# Car-layout_Rev_03_-In_Pros.net
KiCad netlist of a schematic drawn in EAGLE
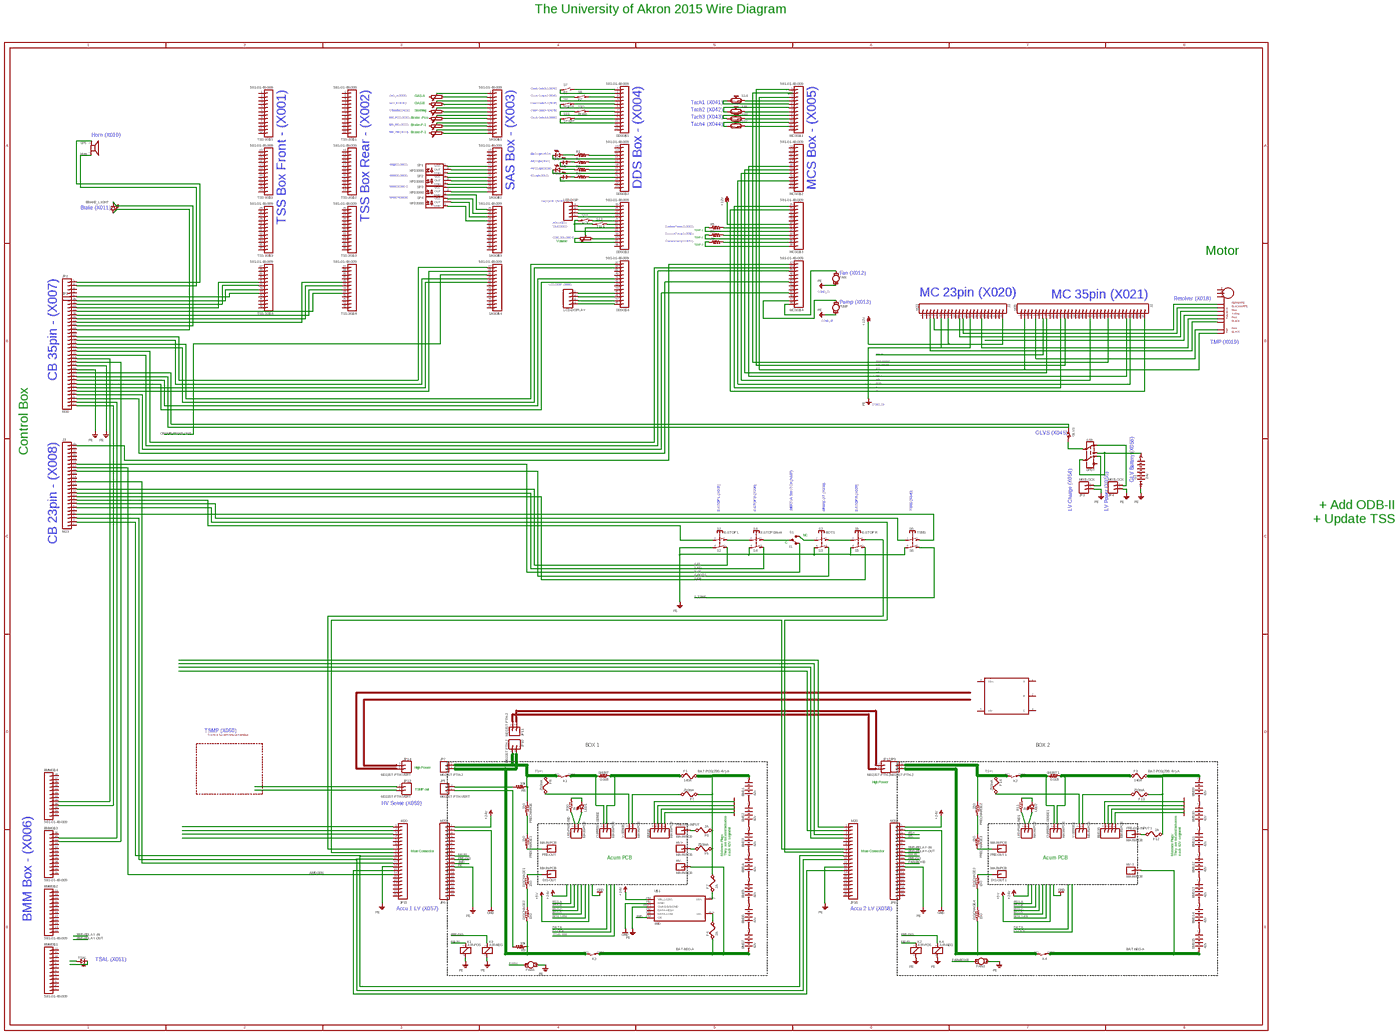
[diagram p0: schematic, sheet 1, overview]
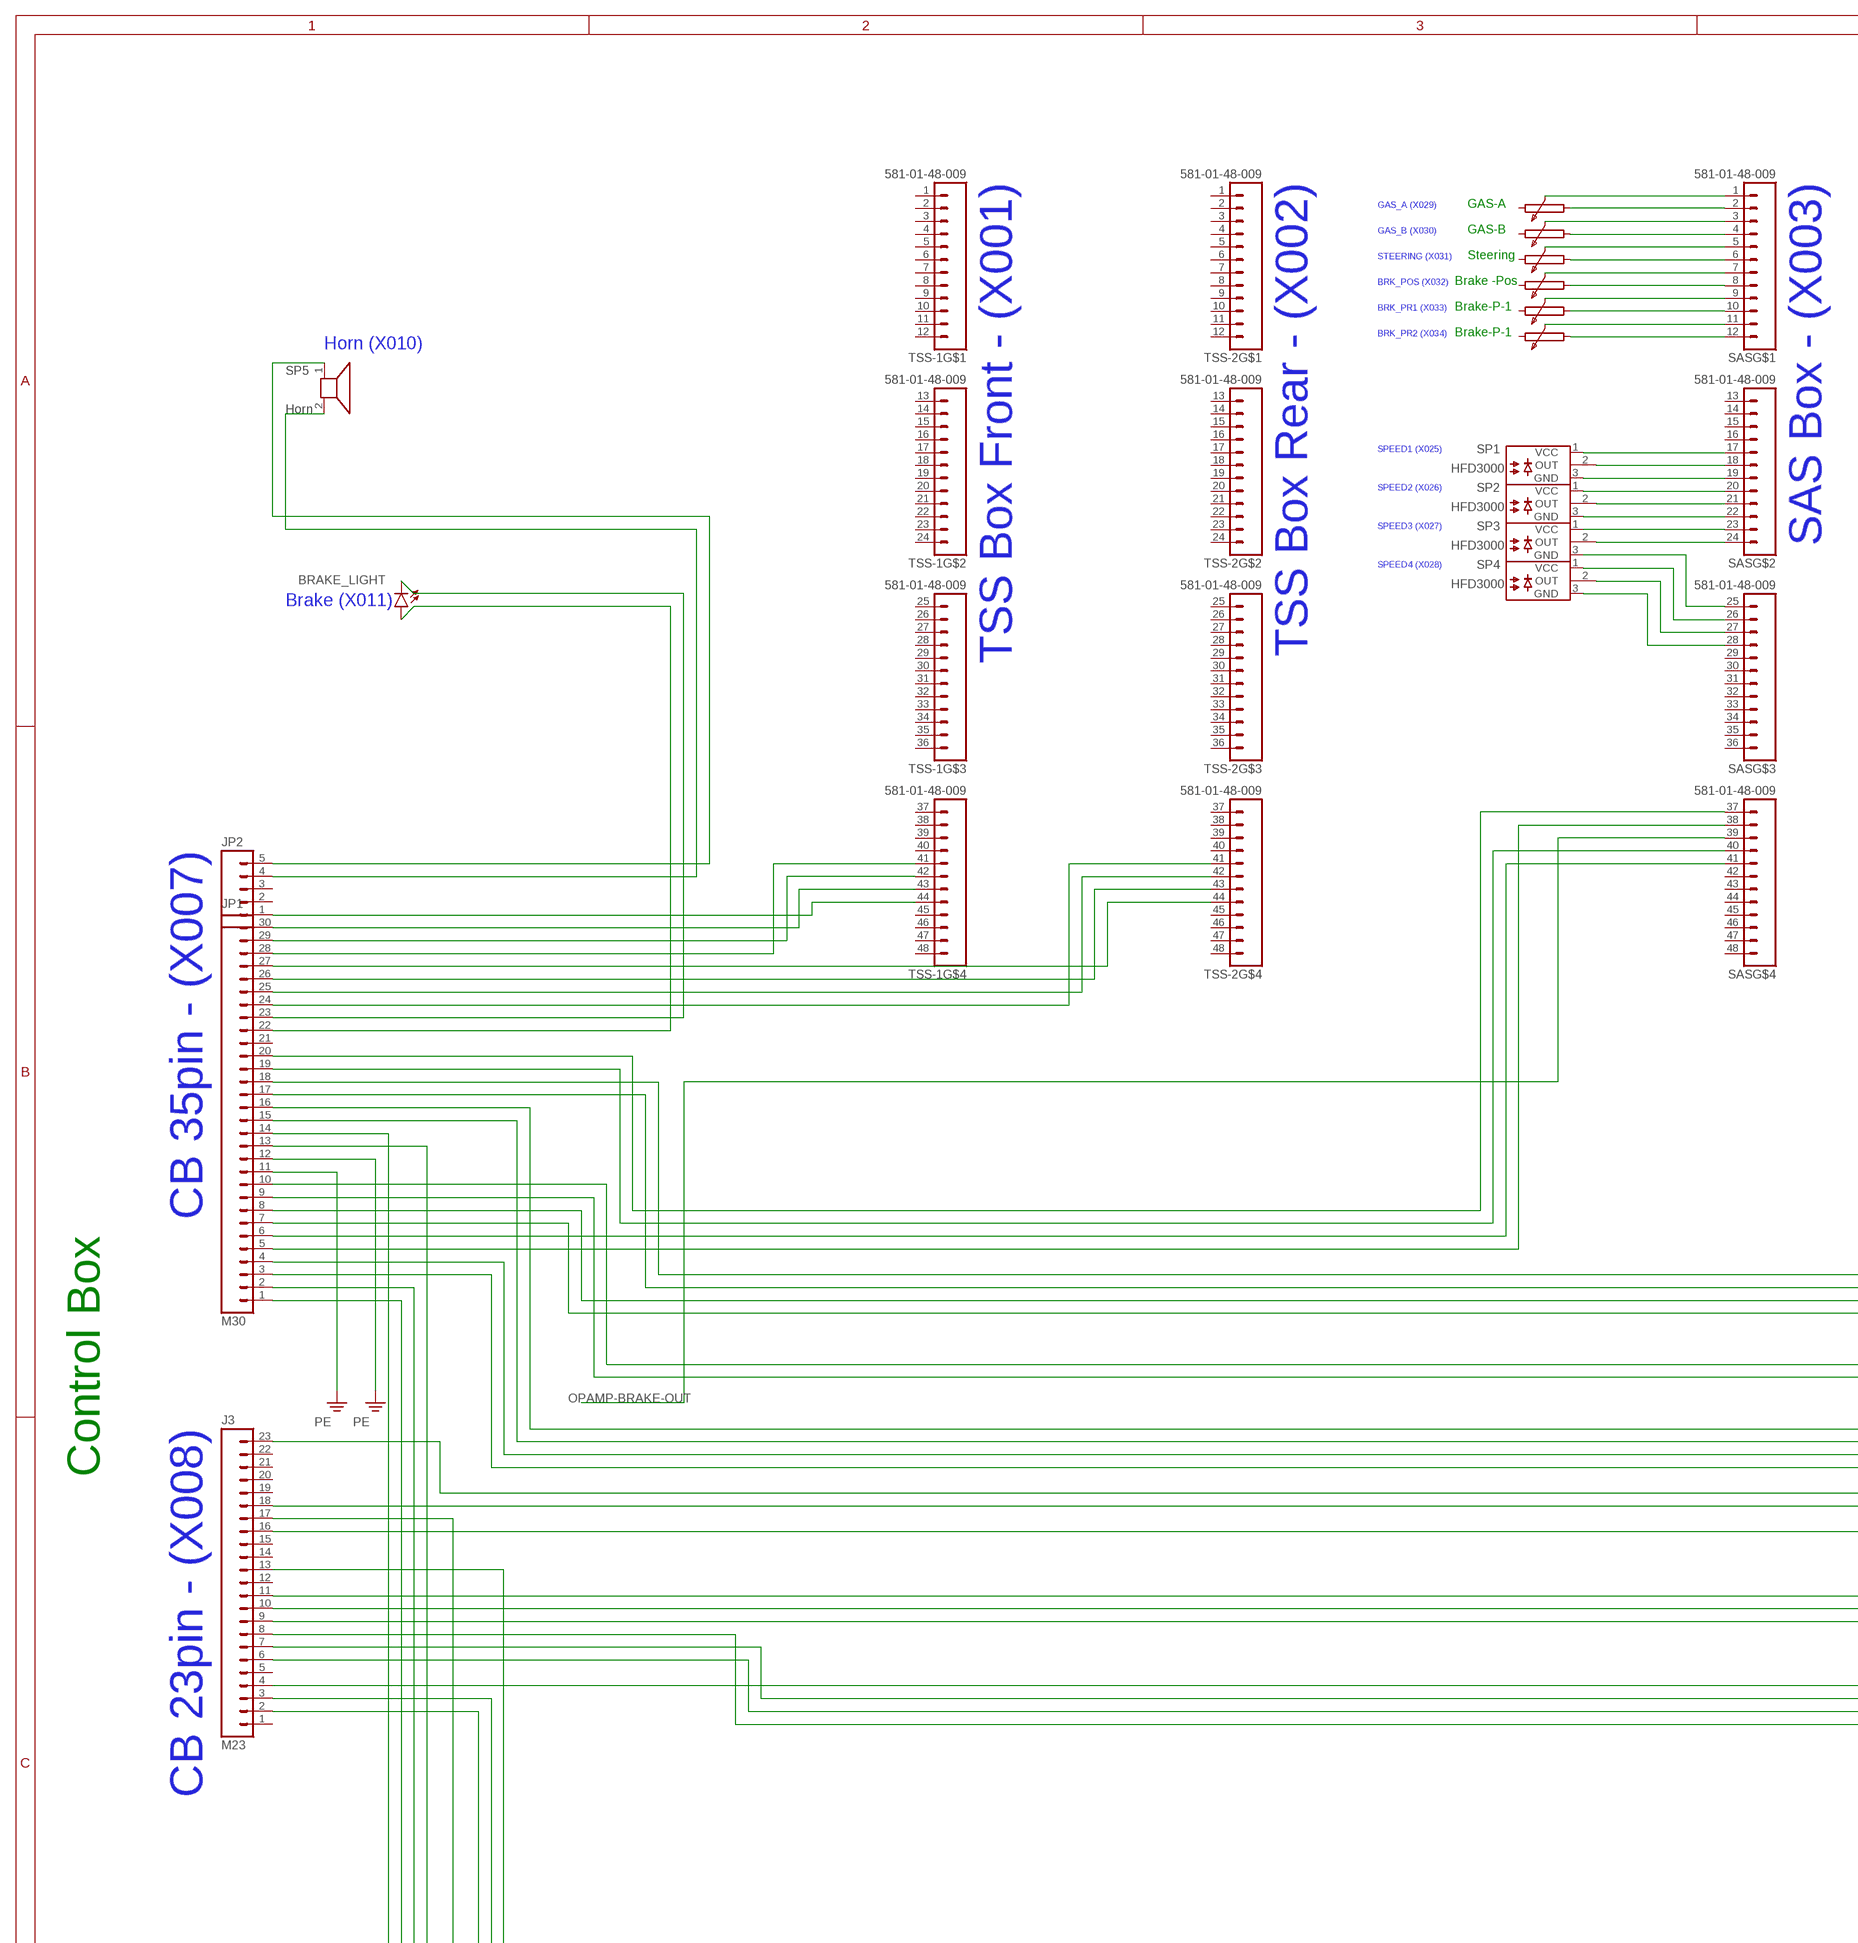
[diagram p1: schematic, sheet 1, part 1 of 6]
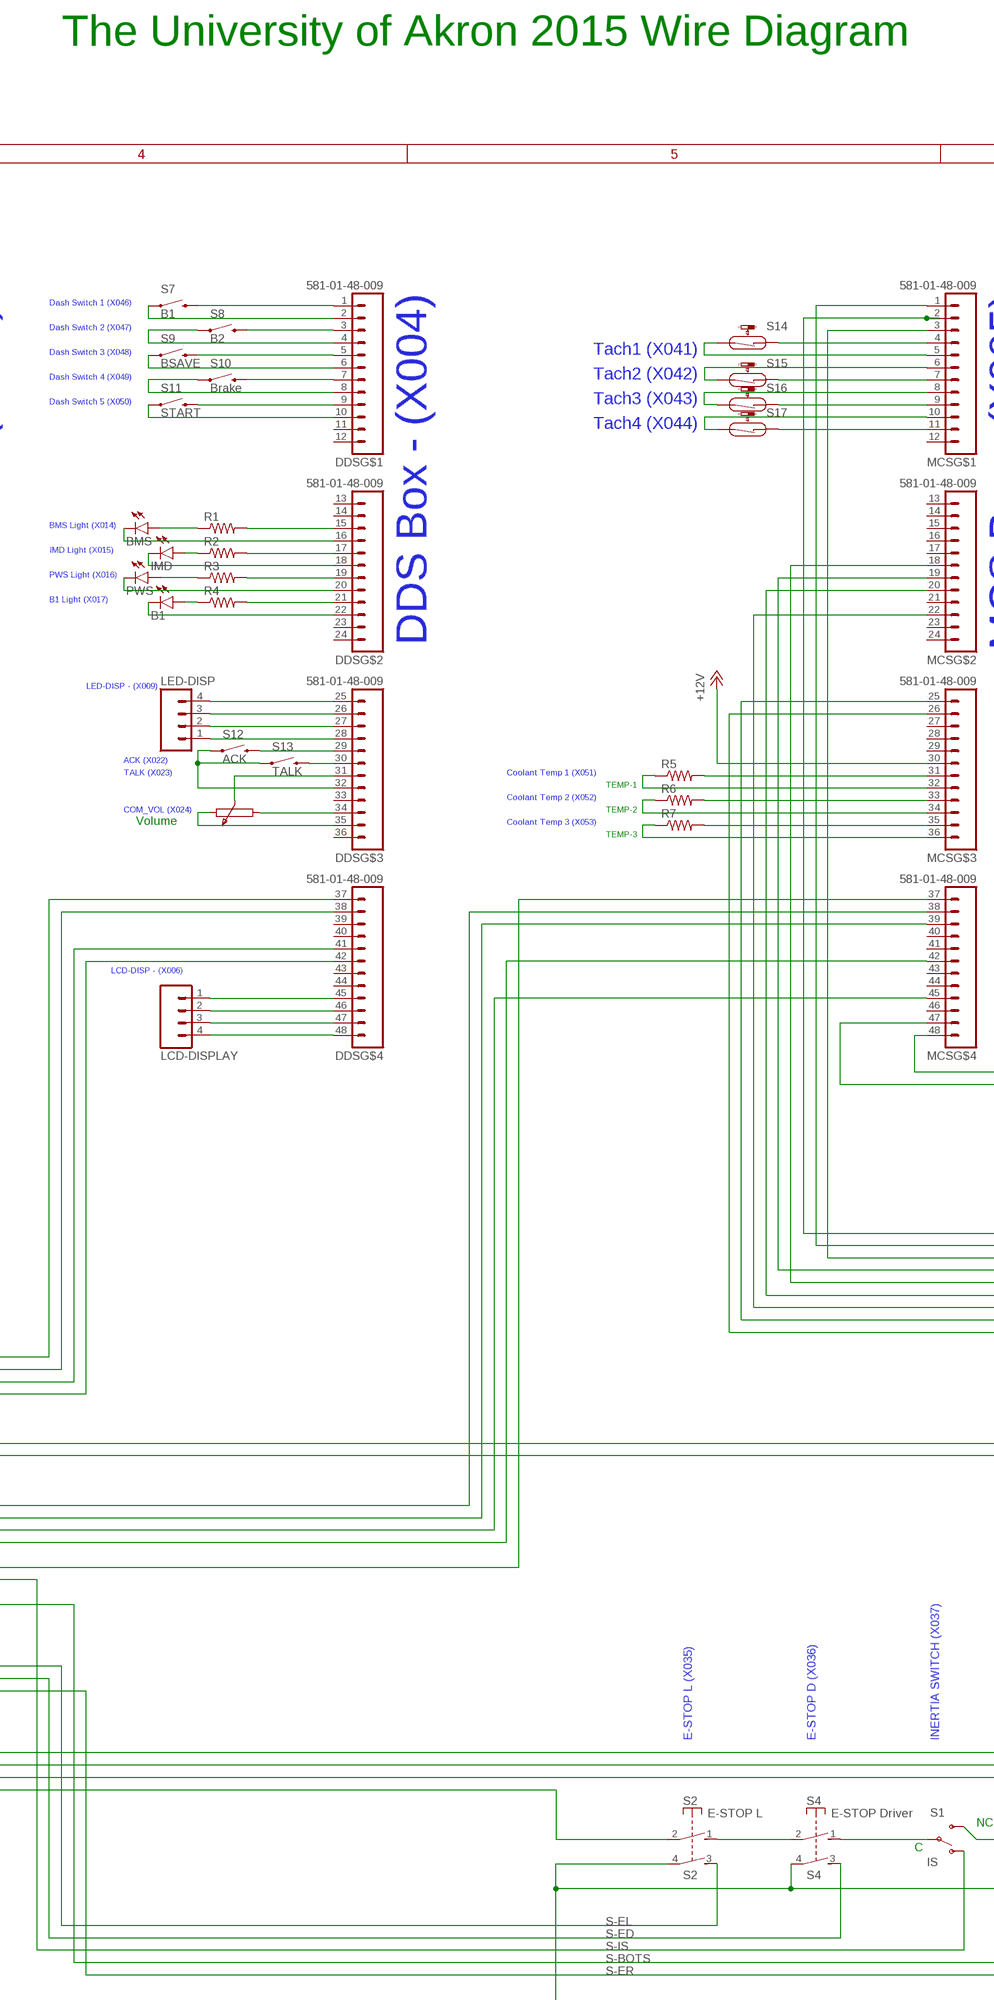
[diagram p2: schematic, sheet 1, part 2 of 6]
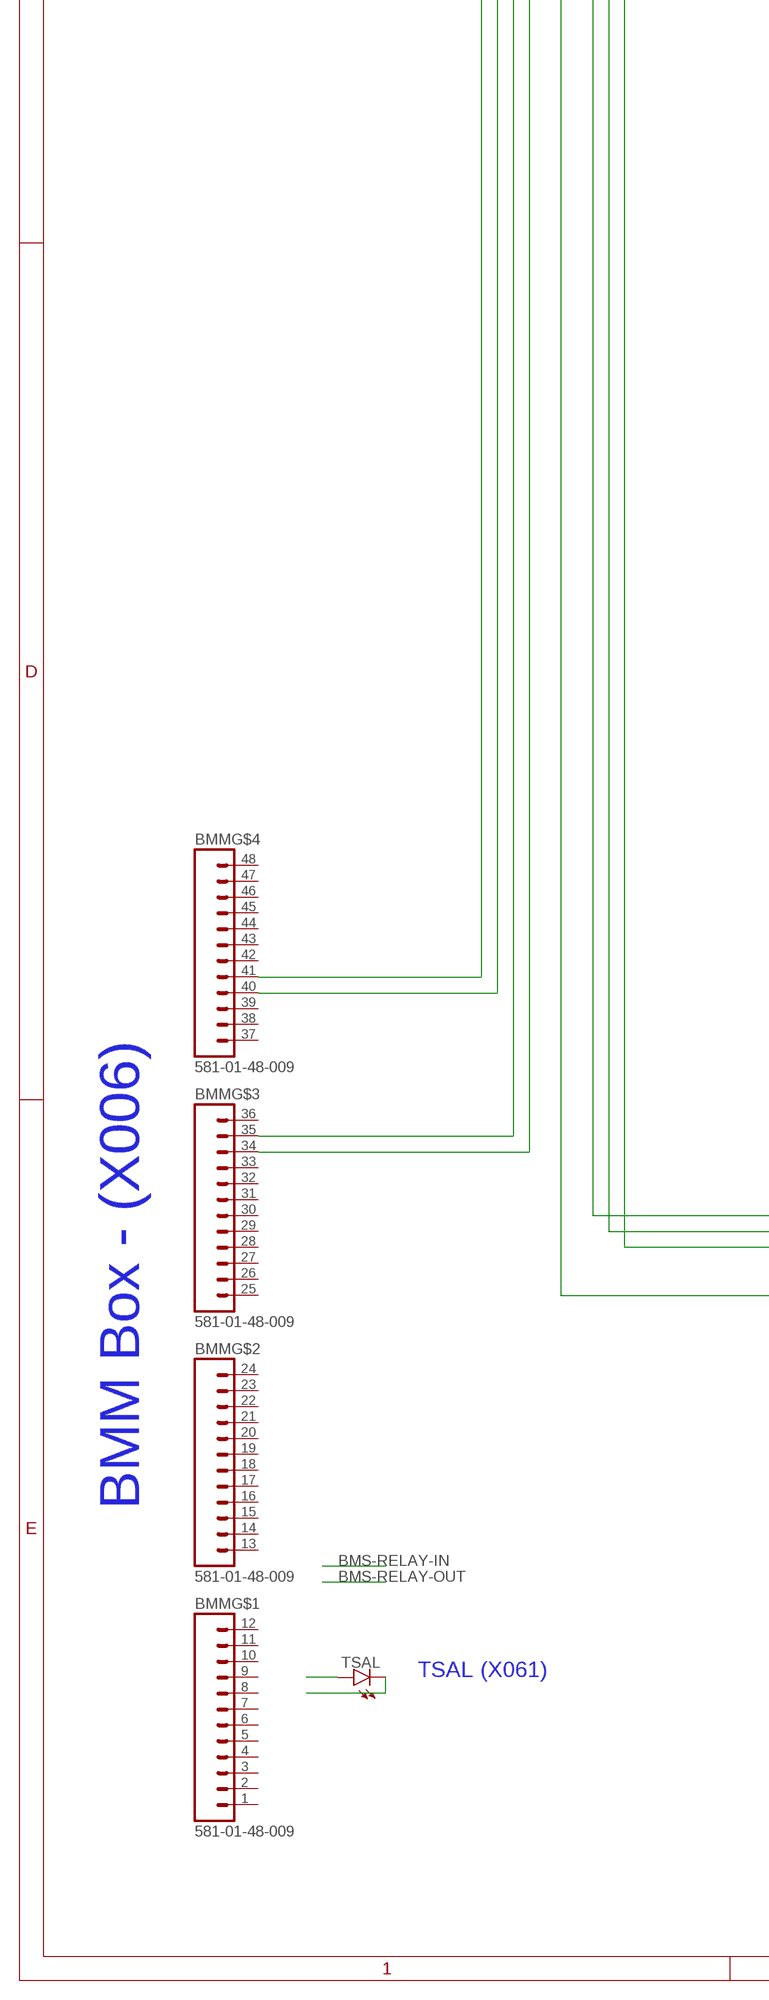
[diagram p3: schematic, sheet 1, part 3 of 6]
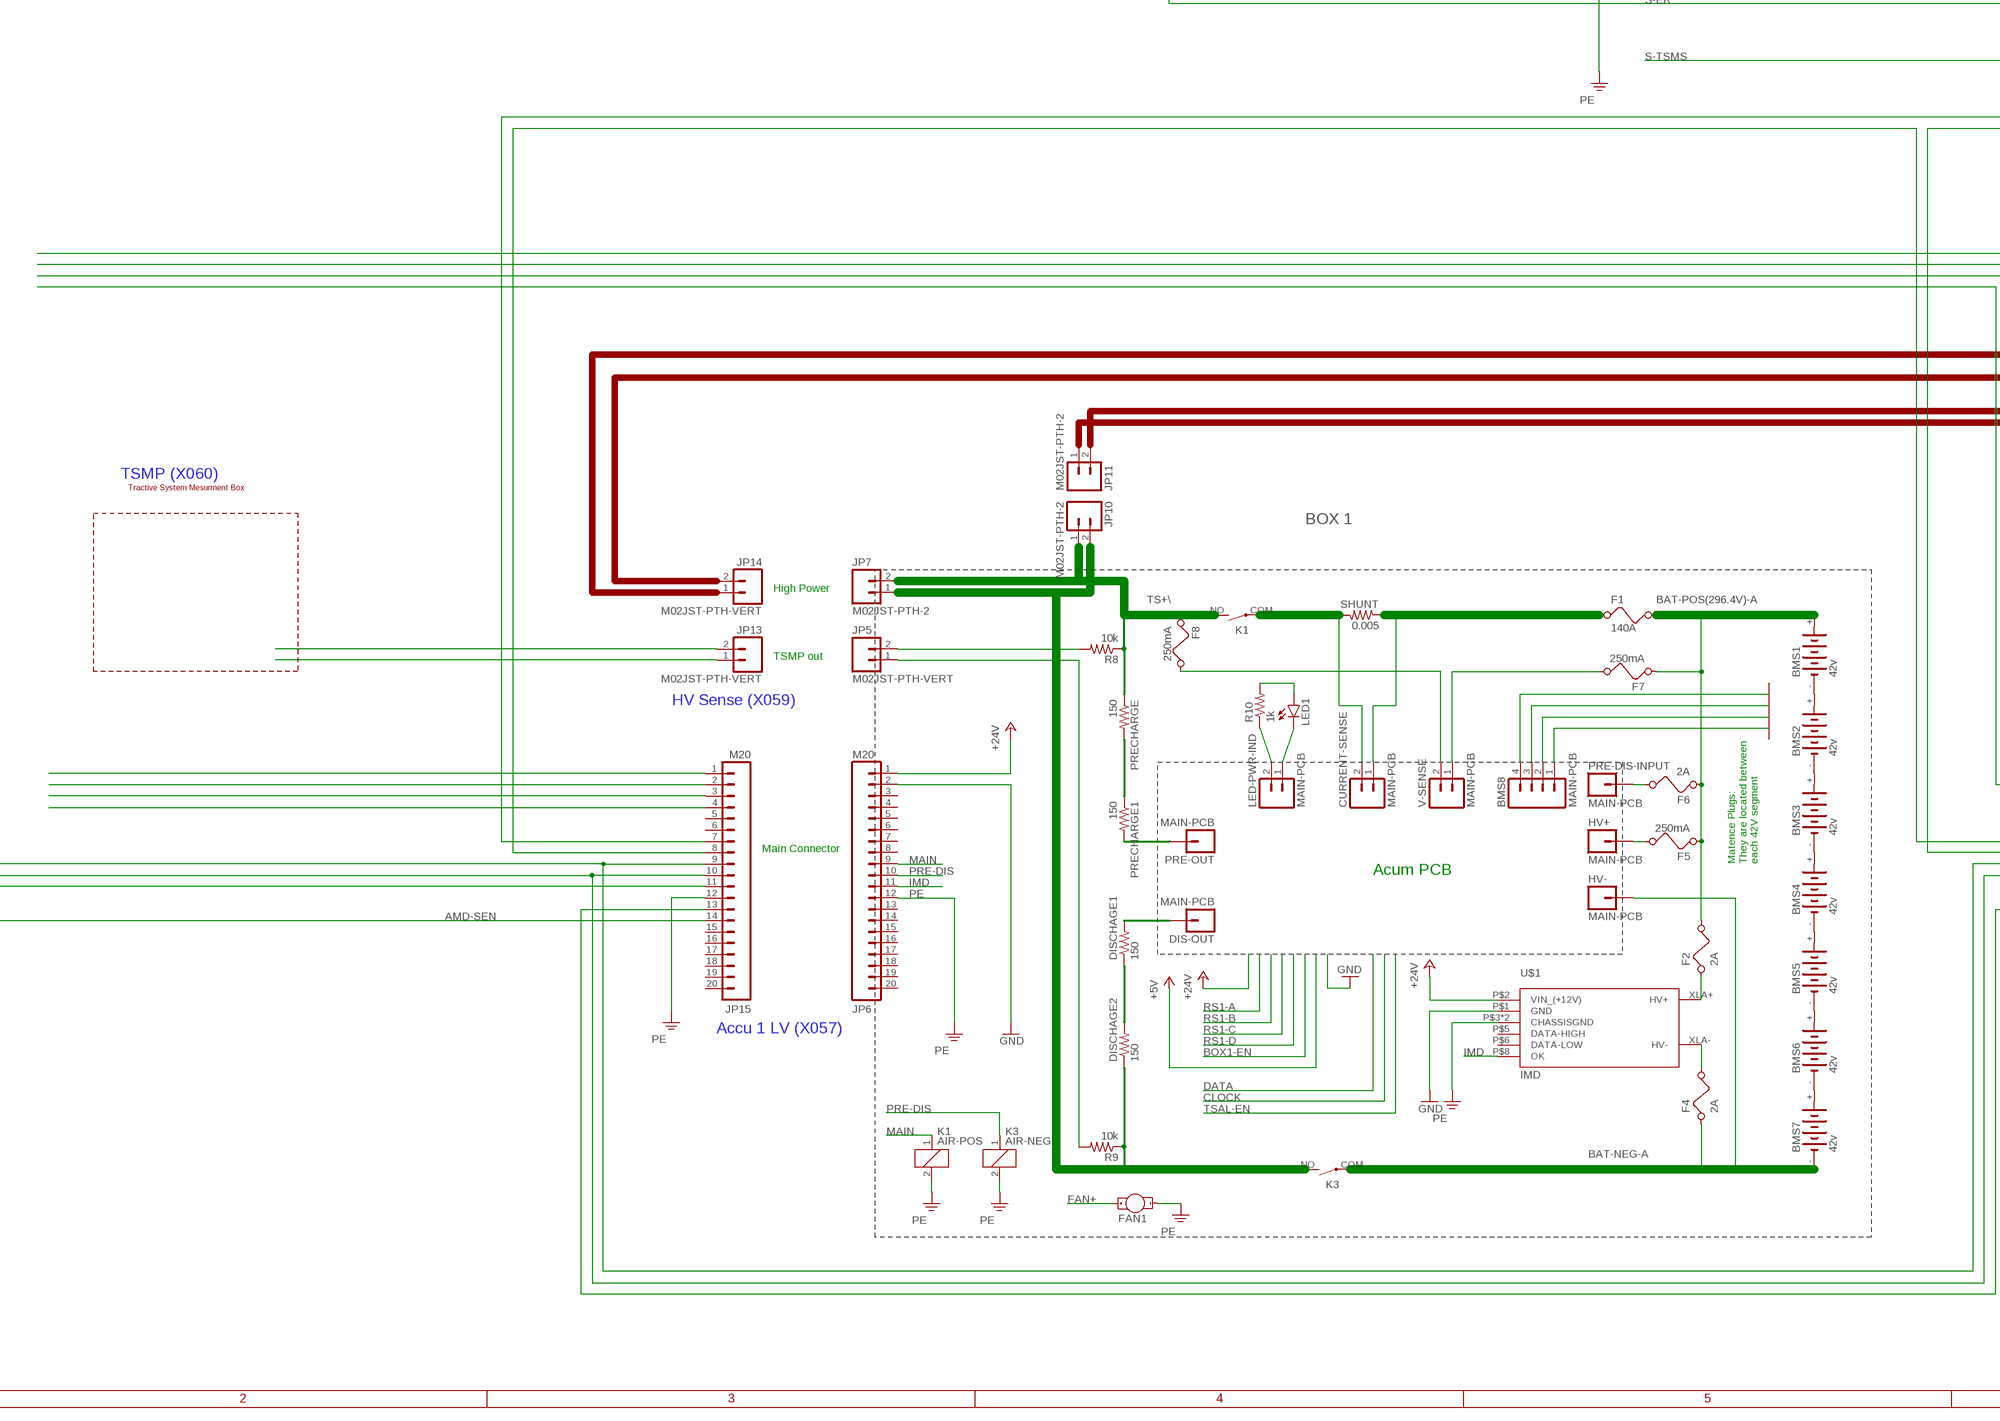
[diagram p4: schematic, sheet 1, part 4 of 6]
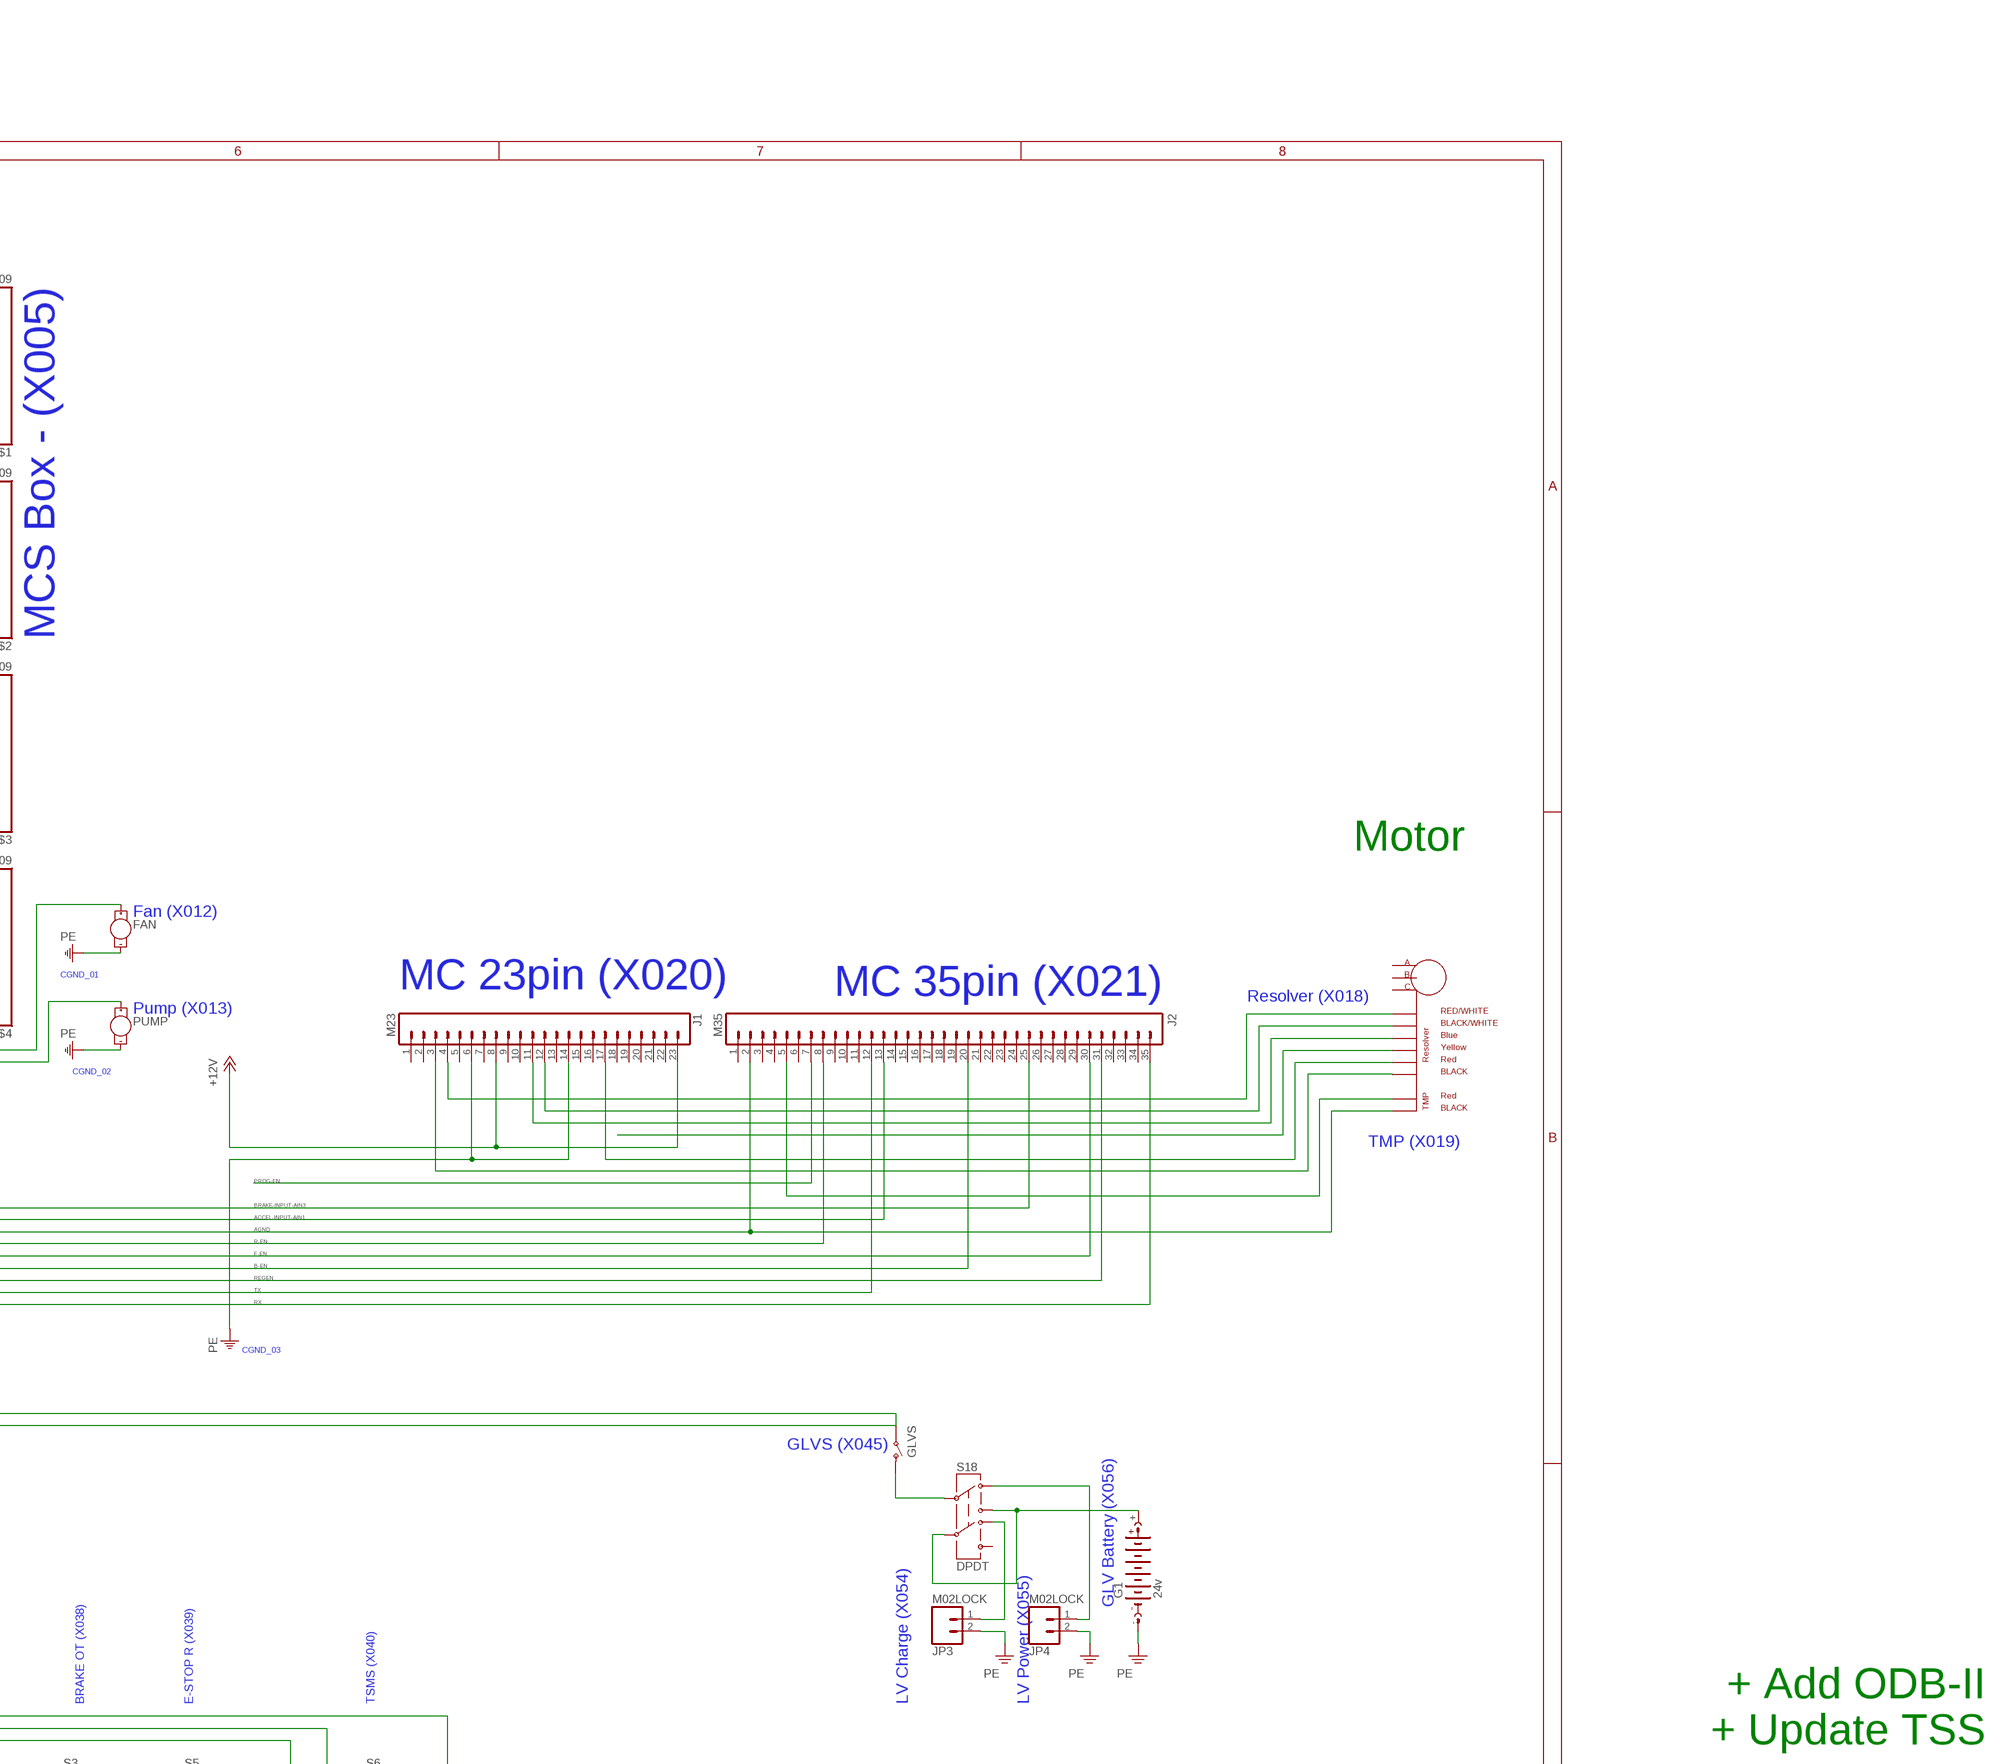
[diagram p5: schematic, sheet 1, part 5 of 6]
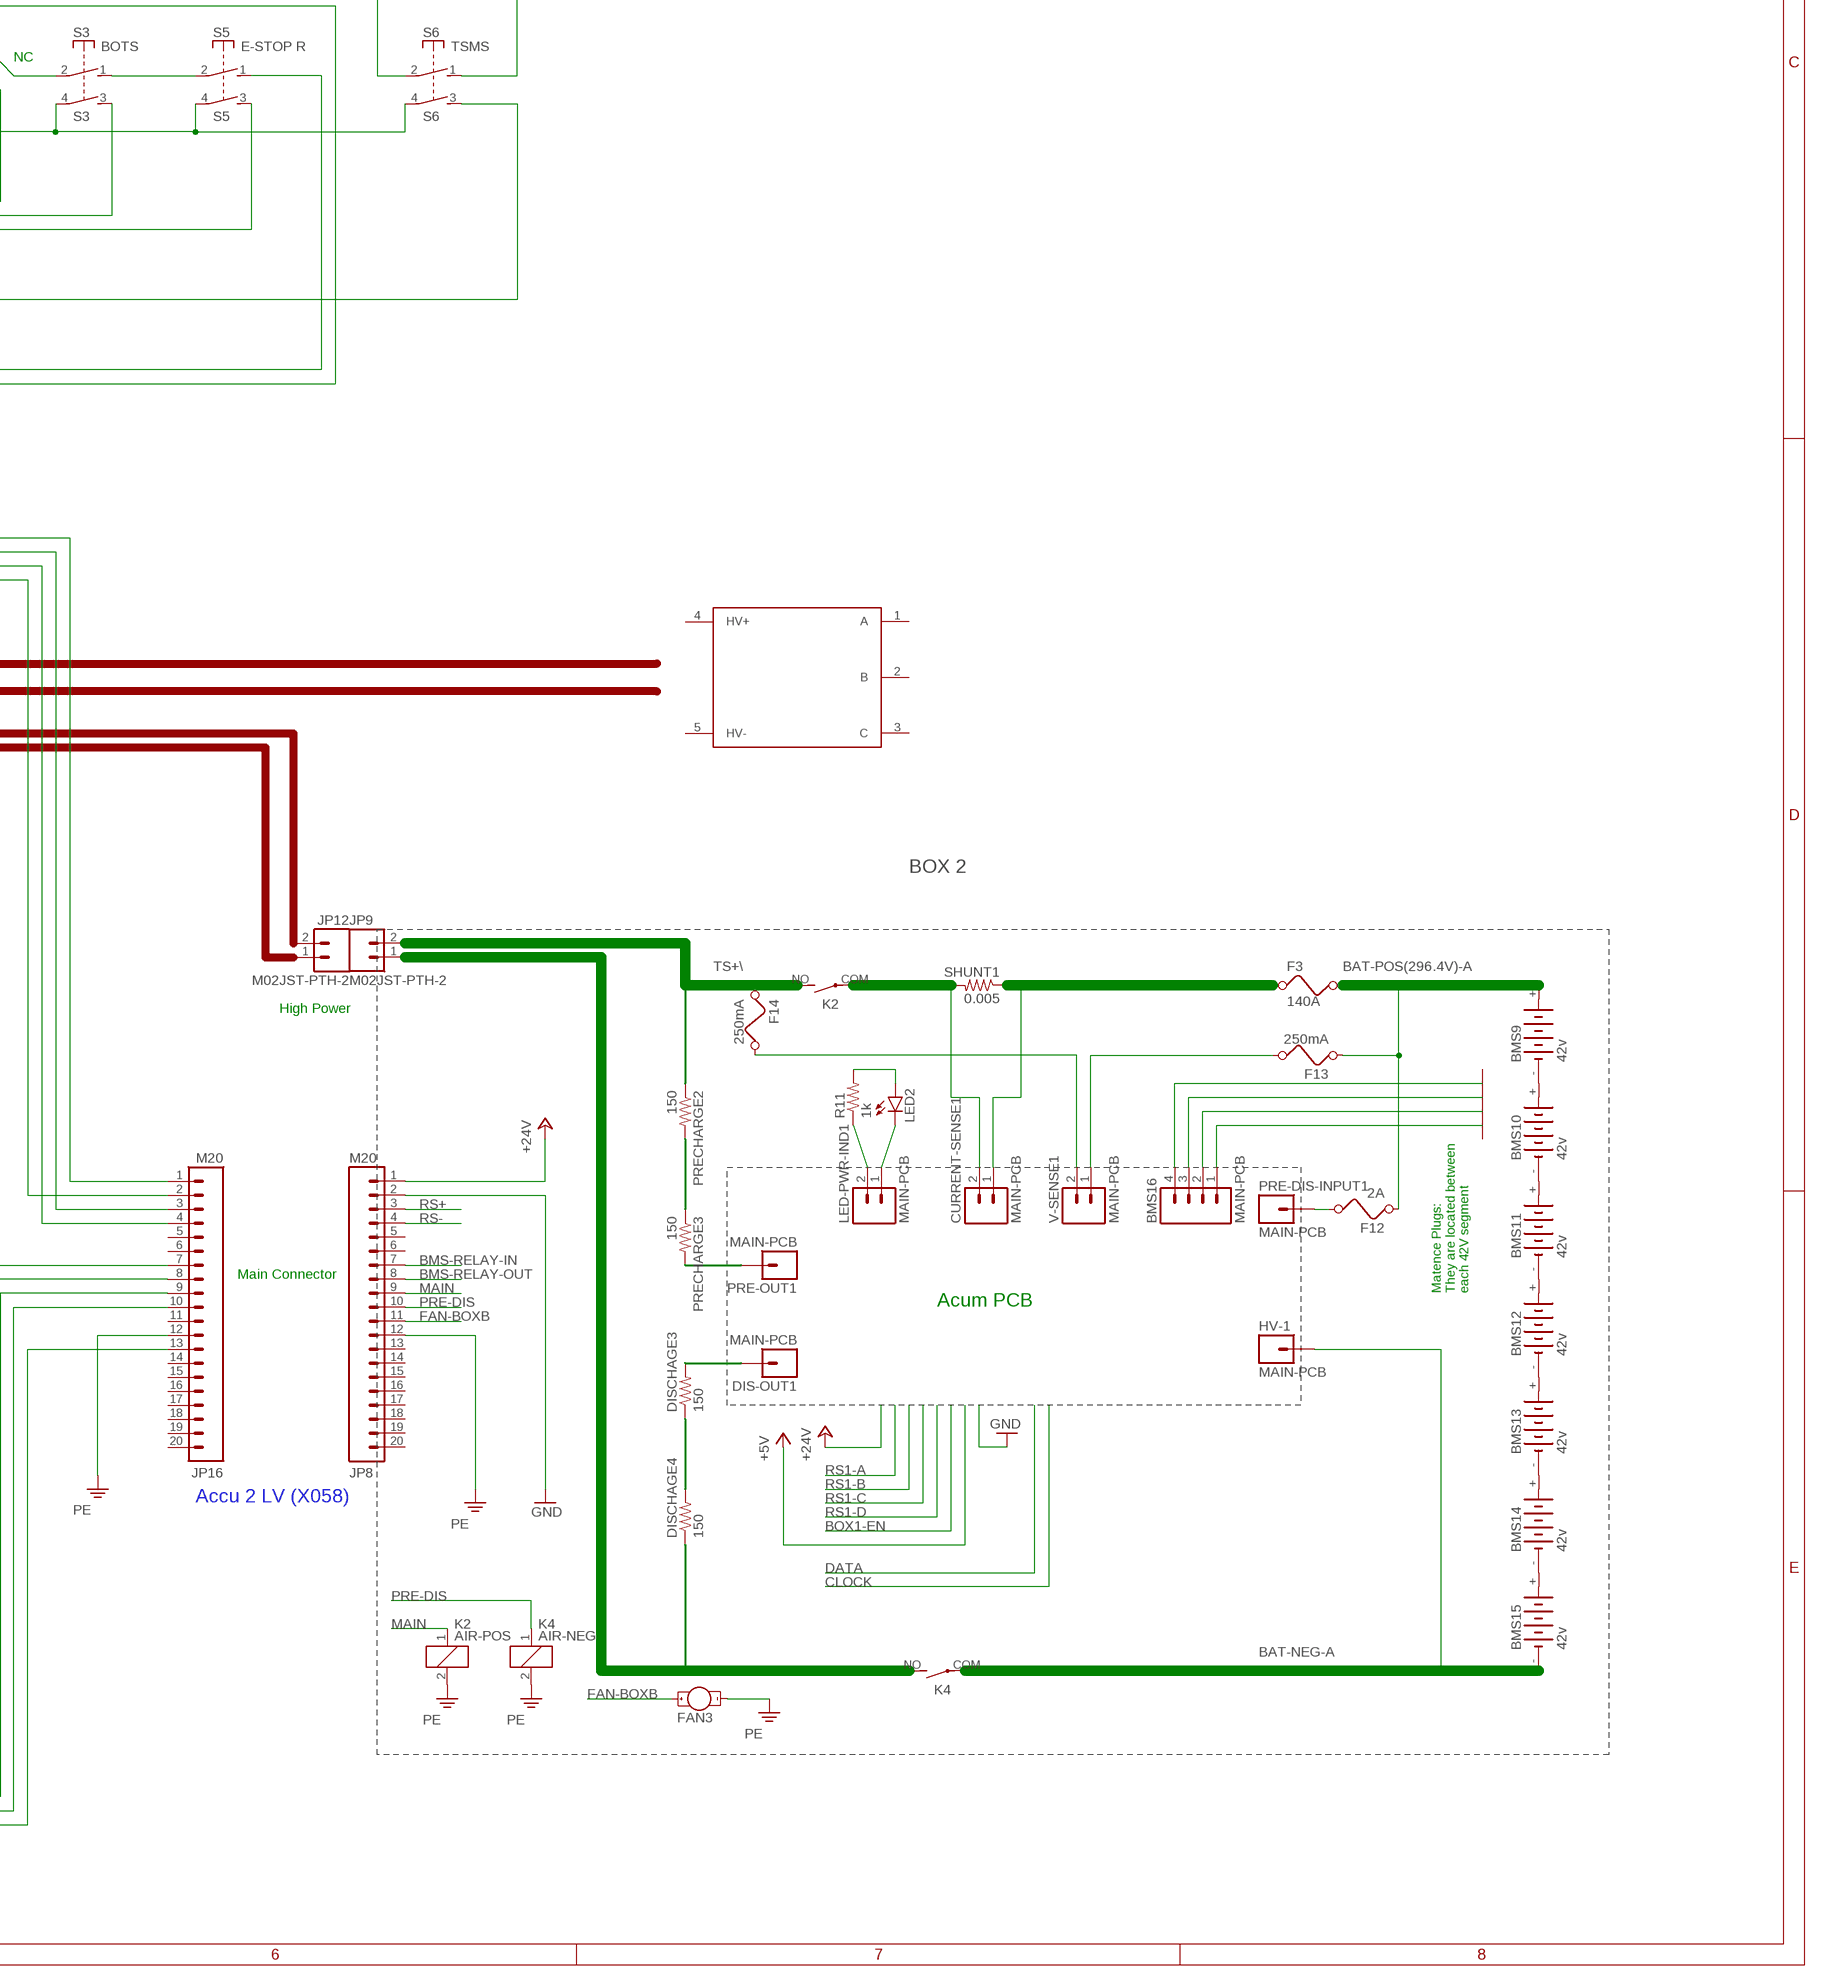
[diagram p6: schematic, sheet 1, part 6 of 6]

(export (version "E")
  (design (tool "Eeschema 10.0.6"))
  (components
    (comp (ref "B1")
      (value "LED5MM")
      (footprint "eagle-import:LED5MM")
      (libsource (lib "eagle-import") (part "LED5MM"))
    )
    (comp (ref "BMM")
      (value "581-01-48-009")
      (footprint "eagle-import:581-01-48-009")
      (libsource (lib "eagle-import") (part "581-01-48-009"))
    )
    (comp (ref "BMS")
      (value "LED5MM")
      (footprint "eagle-import:LED5MM")
      (libsource (lib "eagle-import") (part "LED5MM"))
    )
    (comp (ref "BMS1")
      (value "42v")
      (footprint "eagle-import:VST4")
      (libsource (lib "eagle-import") (part "VST4V8"))
    )
    (comp (ref "BMS2")
      (value "42v")
      (footprint "eagle-import:VST4")
      (libsource (lib "eagle-import") (part "VST4V8"))
    )
    (comp (ref "BMS3")
      (value "42v")
      (footprint "eagle-import:VST4")
      (libsource (lib "eagle-import") (part "VST4V8"))
    )
    (comp (ref "BMS4")
      (value "42v")
      (footprint "eagle-import:VST4")
      (libsource (lib "eagle-import") (part "VST4V8"))
    )
    (comp (ref "BMS5")
      (value "42v")
      (footprint "eagle-import:VST4")
      (libsource (lib "eagle-import") (part "VST4V8"))
    )
    (comp (ref "BMS6")
      (value "42v")
      (footprint "eagle-import:VST4")
      (libsource (lib "eagle-import") (part "VST4V8"))
    )
    (comp (ref "BMS7")
      (value "42v")
      (footprint "eagle-import:VST4")
      (libsource (lib "eagle-import") (part "VST4V8"))
    )
    (comp (ref "BMS8")
      (value "MAIN-PCB")
      (footprint "eagle-import:1X04_LOCK_LONGPADS")
      (libsource (lib "eagle-import") (part "M04LOCK_LONGPADS"))
    )
    (comp (ref "BMS9")
      (value "42v")
      (footprint "eagle-import:VST4")
      (libsource (lib "eagle-import") (part "VST4V8"))
    )
    (comp (ref "BMS10")
      (value "42v")
      (footprint "eagle-import:VST4")
      (libsource (lib "eagle-import") (part "VST4V8"))
    )
    (comp (ref "BMS11")
      (value "42v")
      (footprint "eagle-import:VST4")
      (libsource (lib "eagle-import") (part "VST4V8"))
    )
    (comp (ref "BMS12")
      (value "42v")
      (footprint "eagle-import:VST4")
      (libsource (lib "eagle-import") (part "VST4V8"))
    )
    (comp (ref "BMS13")
      (value "42v")
      (footprint "eagle-import:VST4")
      (libsource (lib "eagle-import") (part "VST4V8"))
    )
    (comp (ref "BMS14")
      (value "42v")
      (footprint "eagle-import:VST4")
      (libsource (lib "eagle-import") (part "VST4V8"))
    )
    (comp (ref "BMS15")
      (value "42v")
      (footprint "eagle-import:VST4")
      (libsource (lib "eagle-import") (part "VST4V8"))
    )
    (comp (ref "BMS16")
      (value "MAIN-PCB")
      (footprint "eagle-import:1X04_LOCK_LONGPADS")
      (libsource (lib "eagle-import") (part "M04LOCK_LONGPADS"))
    )
    (comp (ref "BRAKE_LIGHT")
      (value "LED5MM")
      (footprint "eagle-import:LED5MM")
      (libsource (lib "eagle-import") (part "LED5MM"))
    )
    (comp (ref "CURRENT-SENSE")
      (value "MAIN-PCB")
      (footprint "eagle-import:JST-2-PTH-NS")
      (libsource (lib "eagle-import") (part "M02-JST-2-PTH-NO_SILK"))
    )
    (comp (ref "CURRENT-SENSE1")
      (value "MAIN-PCB")
      (footprint "eagle-import:JST-2-PTH-NS")
      (libsource (lib "eagle-import") (part "M02-JST-2-PTH-NO_SILK"))
    )
    (comp (ref "DDS")
      (value "581-01-48-009")
      (footprint "eagle-import:581-01-48-009")
      (libsource (lib "eagle-import") (part "581-01-48-009"))
    )
    (comp (ref "DIS-OUT")
      (value "MAIN-PCB")
      (footprint "eagle-import:1X01_OFFSET")
      (libsource (lib "eagle-import") (part "M01OFFSET"))
    )
    (comp (ref "DIS-OUT1")
      (value "MAIN-PCB")
      (footprint "eagle-import:1X01_OFFSET")
      (libsource (lib "eagle-import") (part "M01OFFSET"))
    )
    (comp (ref "DISCHAGE1")
      (value "150")
      (footprint "eagle-import:0603-RES")
      (libsource (lib "eagle-import") (part "2.0KOHM1/10W5%(0603)"))
    )
    (comp (ref "DISCHAGE2")
      (value "150")
      (footprint "eagle-import:0603-RES")
      (libsource (lib "eagle-import") (part "2.0KOHM1/10W5%(0603)"))
    )
    (comp (ref "DISCHAGE3")
      (value "150")
      (footprint "eagle-import:0603-RES")
      (libsource (lib "eagle-import") (part "2.0KOHM1/10W5%(0603)"))
    )
    (comp (ref "DISCHAGE4")
      (value "150")
      (footprint "eagle-import:0603-RES")
      (libsource (lib "eagle-import") (part "2.0KOHM1/10W5%(0603)"))
    )
    (comp (ref "F1")
      (value "140A")
      (footprint "eagle-import:FUSE")
      (libsource (lib "eagle-import") (part "FUSE"))
    )
    (comp (ref "F2")
      (value "2A")
      (footprint "eagle-import:FUSE")
      (libsource (lib "eagle-import") (part "FUSE"))
    )
    (comp (ref "F3")
      (value "140A")
      (footprint "eagle-import:FUSE")
      (libsource (lib "eagle-import") (part "FUSE"))
    )
    (comp (ref "F4")
      (value "2A")
      (footprint "eagle-import:FUSE")
      (libsource (lib "eagle-import") (part "FUSE"))
    )
    (comp (ref "F5")
      (value "250mA")
      (footprint "eagle-import:FUSE")
      (libsource (lib "eagle-import") (part "FUSE"))
    )
    (comp (ref "F6")
      (value "2A")
      (footprint "eagle-import:FUSE")
      (libsource (lib "eagle-import") (part "FUSE"))
    )
    (comp (ref "F7")
      (value "250mA")
      (footprint "eagle-import:FUSE")
      (libsource (lib "eagle-import") (part "FUSE"))
    )
    (comp (ref "F8")
      (value "250mA")
      (footprint "eagle-import:FUSE")
      (libsource (lib "eagle-import") (part "FUSE"))
    )
    (comp (ref "F12")
      (value "2A")
      (footprint "eagle-import:FUSE")
      (libsource (lib "eagle-import") (part "FUSE"))
    )
    (comp (ref "F13")
      (value "250mA")
      (footprint "eagle-import:FUSE")
      (libsource (lib "eagle-import") (part "FUSE"))
    )
    (comp (ref "F14")
      (value "250mA")
      (footprint "eagle-import:FUSE")
      (libsource (lib "eagle-import") (part "FUSE"))
    )
    (comp (ref "FAN")
      (value "MOTOR10MM")
      (footprint "eagle-import:VIBE-MOTOR-10MM")
      (libsource (lib "eagle-import") (part "MOTOR10MM"))
    )
    (comp (ref "FAN1")
      (value "MOTOR10MM")
      (footprint "eagle-import:VIBE-MOTOR-10MM")
      (libsource (lib "eagle-import") (part "MOTOR10MM"))
    )
    (comp (ref "FAN3")
      (value "MOTOR10MM")
      (footprint "eagle-import:VIBE-MOTOR-10MM")
      (libsource (lib "eagle-import") (part "MOTOR10MM"))
    )
    (comp (ref "G1")
      (value "24v")
      (footprint "eagle-import:AB9V")
      (libsource (lib "eagle-import") (part "AB9V"))
    )
    (comp (ref "GLVS")
      (value "SWITCH-SPST-2TV")
      (footprint "eagle-import:SWITCH-SPST-VERTICAL")
      (libsource (lib "eagle-import") (part "SWITCH-SPST-2TV"))
    )
    (comp (ref "HV+")
      (value "MAIN-PCB")
      (footprint "eagle-import:1X01_OFFSET")
      (libsource (lib "eagle-import") (part "M01OFFSET"))
    )
    (comp (ref "HV-")
      (value "MAIN-PCB")
      (footprint "eagle-import:1X01_OFFSET")
      (libsource (lib "eagle-import") (part "M01OFFSET"))
    )
    (comp (ref "HV-1")
      (value "MAIN-PCB")
      (footprint "eagle-import:1X01_OFFSET")
      (libsource (lib "eagle-import") (part "M01OFFSET"))
    )
    (comp (ref "IMD")
      (value "LED5MM")
      (footprint "eagle-import:LED5MM")
      (libsource (lib "eagle-import") (part "LED5MM"))
    )
    (comp (ref "J1")
      (value "M23")
      (footprint "eagle-import:1-770669-1")
      (libsource (lib "eagle-import") (part "M23"))
    )
    (comp (ref "J2")
      (value "M35")
      (footprint "eagle-import:1-776163-2")
      (libsource (lib "eagle-import") (part "M35"))
    )
    (comp (ref "J3")
      (value "M23")
      (footprint "eagle-import:1-770669-1")
      (libsource (lib "eagle-import") (part "M23"))
    )
    (comp (ref "JP1")
      (value "M30")
      (footprint "eagle-import:1X30")
      (libsource (lib "eagle-import") (part "M30"))
    )
    (comp (ref "JP2")
      (value "M05LOCK")
      (footprint "eagle-import:1X05_LOCK")
      (libsource (lib "eagle-import") (part "M05LOCK"))
    )
    (comp (ref "JP3")
      (value "M02LOCK")
      (footprint "eagle-import:1X02_LOCK")
      (libsource (lib "eagle-import") (part "M02LOCK"))
    )
    (comp (ref "JP4")
      (value "M02LOCK")
      (footprint "eagle-import:1X02_LOCK")
      (libsource (lib "eagle-import") (part "M02LOCK"))
    )
    (comp (ref "JP5")
      (value "M02JST-PTH-VERT")
      (footprint "eagle-import:JST-2-PTH-VERT")
      (libsource (lib "eagle-import") (part "M02JST-PTH-VERT"))
    )
    (comp (ref "JP6")
      (value "M20")
      (footprint "eagle-import:1X20")
      (libsource (lib "eagle-import") (part "M20"))
    )
    (comp (ref "JP7")
      (value "M02JST-PTH-2")
      (footprint "eagle-import:JST-2-PTH")
      (libsource (lib "eagle-import") (part "M02JST-PTH-2"))
    )
    (comp (ref "JP8")
      (value "M20")
      (footprint "eagle-import:1X20")
      (libsource (lib "eagle-import") (part "M20"))
    )
    (comp (ref "JP9")
      (value "M02JST-PTH-2")
      (footprint "eagle-import:JST-2-PTH")
      (libsource (lib "eagle-import") (part "M02JST-PTH-2"))
    )
    (comp (ref "JP10")
      (value "M02JST-PTH-2")
      (footprint "eagle-import:JST-2-PTH")
      (libsource (lib "eagle-import") (part "M02JST-PTH-2"))
    )
    (comp (ref "JP11")
      (value "M02JST-PTH-2")
      (footprint "eagle-import:JST-2-PTH")
      (libsource (lib "eagle-import") (part "M02JST-PTH-2"))
    )
    (comp (ref "JP12")
      (value "M02JST-PTH-2")
      (footprint "eagle-import:JST-2-PTH")
      (libsource (lib "eagle-import") (part "M02JST-PTH-2"))
    )
    (comp (ref "JP13")
      (value "M02JST-PTH-VERT")
      (footprint "eagle-import:JST-2-PTH-VERT")
      (libsource (lib "eagle-import") (part "M02JST-PTH-VERT"))
    )
    (comp (ref "JP14")
      (value "M02JST-PTH-VERT")
      (footprint "eagle-import:JST-2-PTH-VERT")
      (libsource (lib "eagle-import") (part "M02JST-PTH-VERT"))
    )
    (comp (ref "JP15")
      (value "M20")
      (footprint "eagle-import:1X20")
      (libsource (lib "eagle-import") (part "M20"))
    )
    (comp (ref "JP16")
      (value "M20")
      (footprint "eagle-import:1X20")
      (libsource (lib "eagle-import") (part "M20"))
    )
    (comp (ref "K1")
      (value "AIR-POS")
      (footprint "eagle-import:APF30212A")
      (libsource (lib "eagle-import") (part "APF30212A"))
    )
    (comp (ref "K2")
      (value "AIR-POS")
      (footprint "eagle-import:APF30212A")
      (libsource (lib "eagle-import") (part "APF30212A"))
    )
    (comp (ref "K3")
      (value "AIR-NEG")
      (footprint "eagle-import:APF30212A")
      (libsource (lib "eagle-import") (part "APF30212A"))
    )
    (comp (ref "K4")
      (value "AIR-NEG")
      (footprint "eagle-import:APF30212A")
      (libsource (lib "eagle-import") (part "APF30212A"))
    )
    (comp (ref "LCD-DISPLAY")
      (value "M04LONGPADS")
      (footprint "eagle-import:1X04_LONGPADS")
      (libsource (lib "eagle-import") (part "M04LONGPADS"))
    )
    (comp (ref "LED-DISP")
      (value "M04LONGPADS")
      (footprint "eagle-import:1X04_LONGPADS")
      (libsource (lib "eagle-import") (part "M04LONGPADS"))
    )
    (comp (ref "LED-PWR-IND")
      (value "MAIN-PCB")
      (footprint "eagle-import:JST-2-PTH-NS")
      (libsource (lib "eagle-import") (part "M02-JST-2-PTH-NO_SILK"))
    )
    (comp (ref "LED-PWR-IND1")
      (value "MAIN-PCB")
      (footprint "eagle-import:JST-2-PTH-NS")
      (libsource (lib "eagle-import") (part "M02-JST-2-PTH-NO_SILK"))
    )
    (comp (ref "LED1")
      (value "LED5MM")
      (footprint "eagle-import:LED5MM")
      (libsource (lib "eagle-import") (part "LED5MM"))
    )
    (comp (ref "LED2")
      (value "LED5MM")
      (footprint "eagle-import:LED5MM")
      (libsource (lib "eagle-import") (part "LED5MM"))
    )
    (comp (ref "M1")
      (value "MOTOR-3PHASE")
      (footprint "eagle-import:MC3PHASE")
      (libsource (lib "eagle-import") (part "MOTOR-3PHASE"))
    )
    (comp (ref "MC-1")
      (value "PM100DX")
      (footprint "eagle-import:MC-5")
      (libsource (lib "eagle-import") (part "PM100DX"))
    )
    (comp (ref "MCS")
      (value "581-01-48-009")
      (footprint "eagle-import:581-01-48-009")
      (libsource (lib "eagle-import") (part "581-01-48-009"))
    )
    (comp (ref "PRE-DIS-INPUT")
      (value "MAIN-PCB")
      (footprint "eagle-import:1X01_OFFSET")
      (libsource (lib "eagle-import") (part "M01OFFSET"))
    )
    (comp (ref "PRE-DIS-INPUT1")
      (value "MAIN-PCB")
      (footprint "eagle-import:1X01_OFFSET")
      (libsource (lib "eagle-import") (part "M01OFFSET"))
    )
    (comp (ref "PRE-OUT")
      (value "MAIN-PCB")
      (footprint "eagle-import:1X01_OFFSET")
      (libsource (lib "eagle-import") (part "M01OFFSET"))
    )
    (comp (ref "PRE-OUT1")
      (value "MAIN-PCB")
      (footprint "eagle-import:1X01_OFFSET")
      (libsource (lib "eagle-import") (part "M01OFFSET"))
    )
    (comp (ref "PRECHARGE")
      (value "150")
      (footprint "eagle-import:0603-RES")
      (libsource (lib "eagle-import") (part "2.0KOHM1/10W5%(0603)"))
    )
    (comp (ref "PRECHARGE1")
      (value "150")
      (footprint "eagle-import:0603-RES")
      (libsource (lib "eagle-import") (part "2.0KOHM1/10W5%(0603)"))
    )
    (comp (ref "PRECHARGE2")
      (value "150")
      (footprint "eagle-import:0603-RES")
      (libsource (lib "eagle-import") (part "2.0KOHM1/10W5%(0603)"))
    )
    (comp (ref "PRECHARGE3")
      (value "150")
      (footprint "eagle-import:0603-RES")
      (libsource (lib "eagle-import") (part "2.0KOHM1/10W5%(0603)"))
    )
    (comp (ref "PUMP")
      (value "MOTOR10MM")
      (footprint "eagle-import:VIBE-MOTOR-10MM")
      (libsource (lib "eagle-import") (part "MOTOR10MM"))
    )
    (comp (ref "PWS")
      (value "LED5MM")
      (footprint "eagle-import:LED5MM")
      (libsource (lib "eagle-import") (part "LED5MM"))
    )
    (comp (ref "R1")
      (value "RESISTOR0805-RES")
      (footprint "eagle-import:0805")
      (libsource (lib "eagle-import") (part "RESISTOR0805-RES"))
    )
    (comp (ref "R2")
      (value "RESISTOR0805-RES")
      (footprint "eagle-import:0805")
      (libsource (lib "eagle-import") (part "RESISTOR0805-RES"))
    )
    (comp (ref "R3")
      (value "RESISTOR0805-RES")
      (footprint "eagle-import:0805")
      (libsource (lib "eagle-import") (part "RESISTOR0805-RES"))
    )
    (comp (ref "R4")
      (value "RESISTOR0805-RES")
      (footprint "eagle-import:0805")
      (libsource (lib "eagle-import") (part "RESISTOR0805-RES"))
    )
    (comp (ref "R5")
      (value "RESISTOR0805-RES")
      (footprint "eagle-import:0805")
      (libsource (lib "eagle-import") (part "RESISTOR0805-RES"))
    )
    (comp (ref "R6")
      (value "RESISTOR0805-RES")
      (footprint "eagle-import:0805")
      (libsource (lib "eagle-import") (part "RESISTOR0805-RES"))
    )
    (comp (ref "R7")
      (value "RESISTOR0805-RES")
      (footprint "eagle-import:0805")
      (libsource (lib "eagle-import") (part "RESISTOR0805-RES"))
    )
    (comp (ref "R8")
      (value "10k")
      (footprint "eagle-import:0805")
      (libsource (lib "eagle-import") (part "RESISTOR0805-RES"))
    )
    (comp (ref "R9")
      (value "10k")
      (footprint "eagle-import:0805")
      (libsource (lib "eagle-import") (part "RESISTOR0805-RES"))
    )
    (comp (ref "R10")
      (value "1k")
      (footprint "eagle-import:0603-RES")
      (libsource (lib "eagle-import") (part "2.0KOHM1/10W5%(0603)"))
    )
    (comp (ref "R11")
      (value "1k")
      (footprint "eagle-import:0603-RES")
      (libsource (lib "eagle-import") (part "2.0KOHM1/10W5%(0603)"))
    )
    (comp (ref "S1")
      (value "IS")
      (footprint "eagle-import:SWITCHE-DPDT")
      (libsource (lib "eagle-import") (part "SWITCH-SPDTPTH2"))
    )
    (comp (ref "S2")
      (value "E-STOP L")
      (footprint "eagle-import:PVA1F")
      (libsource (lib "eagle-import") (part "PVA1"))
    )
    (comp (ref "S3")
      (value "BOTS")
      (footprint "eagle-import:PVA1F")
      (libsource (lib "eagle-import") (part "PVA1"))
    )
    (comp (ref "S4")
      (value "E-STOP Driver")
      (footprint "eagle-import:PVA1F")
      (libsource (lib "eagle-import") (part "PVA1"))
    )
    (comp (ref "S5")
      (value "E-STOP R")
      (footprint "eagle-import:PVA1F")
      (libsource (lib "eagle-import") (part "PVA1"))
    )
    (comp (ref "S6")
      (value "TSMS")
      (footprint "eagle-import:PVA1F")
      (libsource (lib "eagle-import") (part "PVA1"))
    )
    (comp (ref "S7")
      (value "B1")
      (footprint "eagle-import:TACTILE-PTH")
      (libsource (lib "eagle-import") (part "SWITCH-MOMENTARY-2PTH"))
    )
    (comp (ref "S8")
      (value "B2")
      (footprint "eagle-import:TACTILE-PTH")
      (libsource (lib "eagle-import") (part "SWITCH-MOMENTARY-2PTH"))
    )
    (comp (ref "S9")
      (value "BSAVE")
      (footprint "eagle-import:TACTILE-PTH")
      (libsource (lib "eagle-import") (part "SWITCH-MOMENTARY-2PTH"))
    )
    (comp (ref "S10")
      (value "Brake")
      (footprint "eagle-import:TACTILE-PTH")
      (libsource (lib "eagle-import") (part "SWITCH-MOMENTARY-2PTH"))
    )
    (comp (ref "S11")
      (value "START")
      (footprint "eagle-import:TACTILE-PTH")
      (libsource (lib "eagle-import") (part "SWITCH-MOMENTARY-2PTH"))
    )
    (comp (ref "S12")
      (value "ACK")
      (footprint "eagle-import:TACTILE-PTH")
      (libsource (lib "eagle-import") (part "SWITCH-MOMENTARY-2PTH"))
    )
    (comp (ref "S13")
      (value "TALK")
      (footprint "eagle-import:TACTILE-PTH")
      (libsource (lib "eagle-import") (part "SWITCH-MOMENTARY-2PTH"))
    )
    (comp (ref "S14")
      (value "REED-SWITCH-CT10-1530-G1")
      (footprint "eagle-import:CT10-G1")
      (fields (field (name "MF") "COTO TECHNOLOGY") (field (name "MPN") "CT10-1530-G1"))
      (libsource (lib "eagle-import") (part "REED-SWITCH-CT10-1530-G1"))
    )
    (comp (ref "S15")
      (value "REED-SWITCH-CT10-1530-G1")
      (footprint "eagle-import:CT10-G1")
      (fields (field (name "MF") "COTO TECHNOLOGY") (field (name "MPN") "CT10-1530-G1"))
      (libsource (lib "eagle-import") (part "REED-SWITCH-CT10-1530-G1"))
    )
    (comp (ref "S16")
      (value "REED-SWITCH-CT10-1530-G1")
      (footprint "eagle-import:CT10-G1")
      (fields (field (name "MF") "COTO TECHNOLOGY") (field (name "MPN") "CT10-1530-G1"))
      (libsource (lib "eagle-import") (part "REED-SWITCH-CT10-1530-G1"))
    )
    (comp (ref "S17")
      (value "REED-SWITCH-CT10-1530-G1")
      (footprint "eagle-import:CT10-G1")
      (fields (field (name "MF") "COTO TECHNOLOGY") (field (name "MPN") "CT10-1530-G1"))
      (libsource (lib "eagle-import") (part "REED-SWITCH-CT10-1530-G1"))
    )
    (comp (ref "S18")
      (value "DPDT")
      (footprint "eagle-import:AYZ0202")
      (libsource (lib "eagle-import") (part "SWITCH-DPDTAYZ0202"))
    )
    (comp (ref "SAS")
      (value "581-01-48-009")
      (footprint "eagle-import:581-01-48-009")
      (libsource (lib "eagle-import") (part "581-01-48-009"))
    )
    (comp (ref "SHUNT")
      (value "0.005")
      (footprint "eagle-import:0603-RES")
      (libsource (lib "eagle-import") (part "2.0KOHM1/10W5%(0603)"))
    )
    (comp (ref "SHUNT1")
      (value "0.005")
      (footprint "eagle-import:0603-RES")
      (libsource (lib "eagle-import") (part "2.0KOHM1/10W5%(0603)"))
    )
    (comp (ref "SP1")
      (value "HFD3000")
      (footprint "eagle-import:TO46-FW3")
      (libsource (lib "eagle-import") (part "HFD3000"))
    )
    (comp (ref "SP2")
      (value "HFD3000")
      (footprint "eagle-import:TO46-FW3")
      (libsource (lib "eagle-import") (part "HFD3000"))
    )
    (comp (ref "SP3")
      (value "HFD3000")
      (footprint "eagle-import:TO46-FW3")
      (libsource (lib "eagle-import") (part "HFD3000"))
    )
    (comp (ref "SP4")
      (value "HFD3000")
      (footprint "eagle-import:TO46-FW3")
      (libsource (lib "eagle-import") (part "HFD3000"))
    )
    (comp (ref "SP5")
      (value "Horn")
      (footprint "eagle-import:AL23P")
      (libsource (lib "eagle-import") (part "AL23P"))
    )
    (comp (ref "TSAL")
      (value "LED5MM")
      (footprint "eagle-import:LED5MM")
      (libsource (lib "eagle-import") (part "LED5MM"))
    )
    (comp (ref "TSS-1")
      (value "581-01-48-009")
      (footprint "eagle-import:581-01-48-009")
      (libsource (lib "eagle-import") (part "581-01-48-009"))
    )
    (comp (ref "TSS-2")
      (value "581-01-48-009")
      (footprint "eagle-import:581-01-48-009")
      (libsource (lib "eagle-import") (part "581-01-48-009"))
    )
    (comp (ref "U$1")
      (value "IMD")
      (footprint "eagle-import:IMD")
      (libsource (lib "eagle-import") (part "IMD"))
    )
    (comp (ref "V-SENSE")
      (value "MAIN-PCB")
      (footprint "eagle-import:JST-2-PTH-NS")
      (libsource (lib "eagle-import") (part "M02-JST-2-PTH-NO_SILK"))
    )
    (comp (ref "V-SENSE1")
      (value "MAIN-PCB")
      (footprint "eagle-import:JST-2-PTH-NS")
      (libsource (lib "eagle-import") (part "M02-JST-2-PTH-NO_SILK"))
    )
  )
  (nets
    (net (code "2") (name "+12V") (class "Default")
      (node (ref "J1") (pin "23") (pinfunction "23_23") (pintype "passive"))
      (node (ref "J1") (pin "8") (pinfunction "8_8") (pintype "passive"))
      (node (ref "MCS") (pin "30") (pinfunction "6_30") (pintype "passive"))
    )
    (net (code "3") (name "+24V") (class "Default")
      (node (ref "JP6") (pin "1") (pinfunction "1_1") (pintype "passive"))
      (node (ref "JP8") (pin "1") (pinfunction "1_1") (pintype "passive"))
      (node (ref "U$1") (pin "P$2") (pinfunction "VIN_(+12V)_P$2") (pintype "bidirectional"))
    )
    (net (code "4") (name "/ACCEL-INPUT-AIN1") (class "Default")
      (node (ref "J2") (pin "13") (pinfunction "13_13") (pintype "passive"))
      (node (ref "MCS") (pin "1") (pinfunction "1_1") (pintype "passive"))
    )
    (net (code "5") (name "/AGND") (class "Default")
      (node (ref "J2") (pin "2") (pinfunction "2_2") (pintype "passive"))
      (node (ref "M1") (pin "9") (pinfunction "P$9_9") (pintype "bidirectional"))
      (node (ref "MCS") (pin "3") (pinfunction "3_3") (pintype "passive"))
    )
    (net (code "6") (name "/AMD-SEN") (class "Default")
      (node (ref "J3") (pin "17") (pinfunction "17_17") (pintype "passive"))
      (node (ref "JP15") (pin "14") (pinfunction "14_14") (pintype "passive"))
    )
    (net (code "7") (name "/B-EN") (class "Default")
      (node (ref "J2") (pin "20") (pinfunction "20_20") (pintype "passive"))
      (node (ref "MCS") (pin "20") (pinfunction "8_20") (pintype "passive"))
    )
    (net (code "8") (name "/BAT-NEG-A") (class "Default")
      (node (ref "BMS15") (pin "-") (pinfunction "-_-") (pintype "passive"))
      (node (ref "BMS7") (pin "-") (pinfunction "-_-") (pintype "passive"))
      (node (ref "F4") (pin "1") (pinfunction "1_1") (pintype "passive"))
      (node (ref "HV-") (pin "1") (pinfunction "1_1") (pintype "passive"))
      (node (ref "HV-1") (pin "1") (pinfunction "1_1") (pintype "passive"))
      (node (ref "K3") (pin "COM") (pinfunction "P_COM") (pintype "passive"))
      (node (ref "K4") (pin "COM") (pinfunction "P_COM") (pintype "passive"))
    )
    (net (code "9") (name "/BAT-POS(296.4V)-A") (class "Default")
      (node (ref "BMS1") (pin "+") (pinfunction "+_+") (pintype "passive"))
      (node (ref "BMS9") (pin "+") (pinfunction "+_+") (pintype "passive"))
      (node (ref "F1") (pin "2") (pinfunction "2_2") (pintype "passive"))
      (node (ref "F12") (pin "1") (pinfunction "1_1") (pintype "passive"))
      (node (ref "F13") (pin "1") (pinfunction "1_1") (pintype "passive"))
      (node (ref "F2") (pin "2") (pinfunction "2_2") (pintype "passive"))
      (node (ref "F3") (pin "2") (pinfunction "2_2") (pintype "passive"))
      (node (ref "F5") (pin "1") (pinfunction "1_1") (pintype "passive"))
      (node (ref "F6") (pin "1") (pinfunction "1_1") (pintype "passive"))
      (node (ref "F7") (pin "1") (pinfunction "1_1") (pintype "passive"))
    )
    (net (code "10") (name "/BMS-RELAY-IN") (class "Default")
      (node (ref "JP8") (pin "7") (pinfunction "7_7") (pintype "passive"))
    )
    (net (code "11") (name "/BMS-RELAY-OUT") (class "Default")
      (node (ref "JP8") (pin "8") (pinfunction "8_8") (pintype "passive"))
    )
    (net (code "13") (name "/BRAKE-INPUT-AIN3") (class "Default")
      (node (ref "J2") (pin "25") (pinfunction "25_25") (pintype "passive"))
      (node (ref "MCS") (pin "2") (pinfunction "2_2") (pintype "passive"))
    )
    (net (code "16") (name "/F-EN") (class "Default")
      (node (ref "J2") (pin "30") (pinfunction "30_30") (pintype "passive"))
      (node (ref "MCS") (pin "18") (pinfunction "6_18") (pintype "passive"))
    )
    (net (code "17") (name "/FAN+") (class "Default")
      (node (ref "FAN1") (pin "+") (pinfunction "+_+") (pintype "bidirectional"))
    )
    (net (code "18") (name "/FAN-BOXB") (class "Default")
      (node (ref "FAN3") (pin "+") (pinfunction "+_+") (pintype "bidirectional"))
      (node (ref "JP8") (pin "11") (pinfunction "11_11") (pintype "passive"))
    )
    (net (code "19") (name "/IMD") (class "Default")
      (node (ref "JP6") (pin "11") (pinfunction "11_11") (pintype "passive"))
      (node (ref "U$1") (pin "P$8") (pinfunction "OK_P$8") (pintype "bidirectional"))
    )
    (net (code "20") (name "/MAIN") (class "Default")
      (node (ref "JP6") (pin "9") (pinfunction "9_9") (pintype "passive"))
      (node (ref "JP8") (pin "9") (pinfunction "9_9") (pintype "passive"))
      (node (ref "K1") (pin "1") (pinfunction "1_1") (pintype "passive"))
      (node (ref "K2") (pin "1") (pinfunction "1_1") (pintype "passive"))
    )
    (net (code "21") (name "/OPAMP-BRAKE-OUT") (class "Default")
      (node (ref "SAS") (pin "39") (pinfunction "3_39") (pintype "passive"))
    )
    (net (code "22") (name "/PRE-DIS") (class "Default")
      (node (ref "JP6") (pin "10") (pinfunction "10_10") (pintype "passive"))
      (node (ref "JP8") (pin "10") (pinfunction "10_10") (pintype "passive"))
      (node (ref "K3") (pin "1") (pinfunction "1_1") (pintype "passive"))
      (node (ref "K4") (pin "1") (pinfunction "1_1") (pintype "passive"))
    )
    (net (code "23") (name "/PROG-EN") (class "Default")
      (node (ref "J2") (pin "7") (pinfunction "7_7") (pintype "passive"))
    )
    (net (code "24") (name "/R-EN") (class "Default")
      (node (ref "J2") (pin "8") (pinfunction "8_8") (pintype "passive"))
      (node (ref "MCS") (pin "19") (pinfunction "7_19") (pintype "passive"))
    )
    (net (code "25") (name "/REGEN") (class "Default")
      (node (ref "J2") (pin "31") (pinfunction "31_31") (pintype "passive"))
      (node (ref "MCS") (pin "22") (pinfunction "10_22") (pintype "passive"))
    )
    (net (code "26") (name "/RS+") (class "Default")
      (node (ref "JP8") (pin "3") (pinfunction "3_3") (pintype "passive"))
    )
    (net (code "27") (name "/RS-") (class "Default")
      (node (ref "JP8") (pin "4") (pinfunction "4_4") (pintype "passive"))
    )
    (net (code "32") (name "/RX") (class "Default")
      (node (ref "J2") (pin "35") (pinfunction "35_35") (pintype "passive"))
      (node (ref "MCS") (pin "26") (pinfunction "2_26") (pintype "passive"))
    )
    (net (code "33") (name "/S-BOTS") (class "Default")
      (node (ref "J3") (pin "16") (pinfunction "16_16") (pintype "passive"))
      (node (ref "S3") (pin "3") (pinfunction "S_3") (pintype "passive"))
    )
    (net (code "34") (name "/S-ED") (class "Default")
      (node (ref "J3") (pin "10") (pinfunction "10_10") (pintype "passive"))
      (node (ref "S4") (pin "3") (pinfunction "S_3") (pintype "passive"))
    )
    (net (code "35") (name "/S-EL") (class "Default")
      (node (ref "J3") (pin "11") (pinfunction "11_11") (pintype "passive"))
      (node (ref "S2") (pin "3") (pinfunction "S_3") (pintype "passive"))
    )
    (net (code "36") (name "/S-ER") (class "Default")
      (node (ref "J3") (pin "9") (pinfunction "9_9") (pintype "passive"))
      (node (ref "S5") (pin "3") (pinfunction "S_3") (pintype "passive"))
    )
    (net (code "37") (name "/S-IS") (class "Default")
      (node (ref "J3") (pin "18") (pinfunction "18_18") (pintype "passive"))
      (node (ref "S1") (pin "1") (pinfunction "O_1") (pintype "passive"))
    )
    (net (code "38") (name "/S-TSMS") (class "Default")
      (node (ref "S6") (pin "3") (pinfunction "S_3") (pintype "passive"))
    )
    (net (code "39") (name "/TS+\\") (class "Default")
      (node (ref "F14") (pin "1") (pinfunction "1_1") (pintype "passive"))
      (node (ref "F8") (pin "1") (pinfunction "1_1") (pintype "passive"))
      (node (ref "JP10") (pin "1") (pinfunction "1_1") (pintype "passive"))
      (node (ref "JP7") (pin "2") (pinfunction "2_2") (pintype "passive"))
      (node (ref "JP9") (pin "2") (pinfunction "2_2") (pintype "passive"))
      (node (ref "K1") (pin "NO") (pinfunction "S_NO") (pintype "passive"))
      (node (ref "K2") (pin "NO") (pinfunction "S_NO") (pintype "passive"))
      (node (ref "PRECHARGE") (pin "1") (pinfunction "1_1") (pintype "passive"))
      (node (ref "PRECHARGE2") (pin "1") (pinfunction "1_1") (pintype "passive"))
      (node (ref "R8") (pin "1") (pinfunction "1_1") (pintype "passive"))
    )
    (net (code "41") (name "/TX") (class "Default")
      (node (ref "J2") (pin "12") (pinfunction "12_12") (pintype "passive"))
      (node (ref "MCS") (pin "25") (pinfunction "1_25") (pintype "passive"))
    )
    (net (code "42") (name "GND") (class "Default")
      (node (ref "JP6") (pin "2") (pinfunction "2_2") (pintype "passive"))
      (node (ref "JP8") (pin "2") (pinfunction "2_2") (pintype "passive"))
      (node (ref "U$1") (pin "P$1") (pinfunction "GND_P$1") (pintype "bidirectional"))
    )
    (net (code "43") (name "Net-(B1-C)") (class "Default")
      (node (ref "B1") (pin "K") (pinfunction "C_K") (pintype "passive"))
      (node (ref "DDS") (pin "22") (pinfunction "10_22") (pintype "passive"))
    )
    (net (code "44") (name "Net-(B1-PadA)") (class "Default")
      (node (ref "B1") (pin "A") (pinfunction "A_A") (pintype "passive"))
      (node (ref "R4") (pin "1") (pinfunction "1_1") (pintype "passive"))
    )
    (net (code "45") (name "Net-(BMMC-10)") (class "Default")
      (node (ref "BMM") (pin "34") (pinfunction "10_34") (pintype "passive"))
      (node (ref "JP1") (pin "13") (pinfunction "13_13") (pintype "passive"))
    )
    (net (code "46") (name "Net-(BMMC-11)") (class "Default")
      (node (ref "BMM") (pin "35") (pinfunction "11_35") (pintype "passive"))
      (node (ref "JP1") (pin "2") (pinfunction "2_2") (pintype "passive"))
    )
    (net (code "47") (name "Net-(BMMD-4)") (class "Default")
      (node (ref "BMM") (pin "40") (pinfunction "4_40") (pintype "passive"))
      (node (ref "JP1") (pin "1") (pinfunction "1_1") (pintype "passive"))
    )
    (net (code "48") (name "Net-(BMMD-5)") (class "Default")
      (node (ref "BMM") (pin "41") (pinfunction "5_41") (pintype "passive"))
      (node (ref "JP1") (pin "14") (pinfunction "14_14") (pintype "passive"))
    )
    (net (code "49") (name "Net-(BMS-C)") (class "Default")
      (node (ref "BMS") (pin "K") (pinfunction "C_K") (pintype "passive"))
      (node (ref "DDS") (pin "16") (pinfunction "4_16") (pintype "passive"))
    )
    (net (code "50") (name "Net-(BMS-PadA)") (class "Default")
      (node (ref "BMS") (pin "A") (pinfunction "A_A") (pintype "passive"))
      (node (ref "R1") (pin "1") (pinfunction "1_1") (pintype "passive"))
    )
    (net (code "51") (name "Net-(BMS1-Pad-)") (class "Default")
      (node (ref "BMS1") (pin "-") (pinfunction "-_-") (pintype "passive"))
      (node (ref "BMS2") (pin "+") (pinfunction "+_+") (pintype "passive"))
    )
    (net (code "52") (name "Net-(BMS2-Pad-)") (class "Default")
      (node (ref "BMS2") (pin "-") (pinfunction "-_-") (pintype "passive"))
      (node (ref "BMS3") (pin "+") (pinfunction "+_+") (pintype "passive"))
    )
    (net (code "53") (name "Net-(BMS3-Pad-)") (class "Default")
      (node (ref "BMS3") (pin "-") (pinfunction "-_-") (pintype "passive"))
      (node (ref "BMS4") (pin "+") (pinfunction "+_+") (pintype "passive"))
    )
    (net (code "54") (name "Net-(BMS4-Pad-)") (class "Default")
      (node (ref "BMS4") (pin "-") (pinfunction "-_-") (pintype "passive"))
      (node (ref "BMS5") (pin "+") (pinfunction "+_+") (pintype "passive"))
    )
    (net (code "55") (name "Net-(BMS5-Pad-)") (class "Default")
      (node (ref "BMS5") (pin "-") (pinfunction "-_-") (pintype "passive"))
      (node (ref "BMS6") (pin "+") (pinfunction "+_+") (pintype "passive"))
    )
    (net (code "56") (name "Net-(BMS6-Pad-)") (class "Default")
      (node (ref "BMS6") (pin "-") (pinfunction "-_-") (pintype "passive"))
      (node (ref "BMS7") (pin "+") (pinfunction "+_+") (pintype "passive"))
    )
    (net (code "57") (name "Net-(BMS10-Pad+)") (class "Default")
      (node (ref "BMS10") (pin "+") (pinfunction "+_+") (pintype "passive"))
      (node (ref "BMS9") (pin "-") (pinfunction "-_-") (pintype "passive"))
    )
    (net (code "58") (name "Net-(BMS10-Pad-)") (class "Default")
      (node (ref "BMS10") (pin "-") (pinfunction "-_-") (pintype "passive"))
      (node (ref "BMS11") (pin "+") (pinfunction "+_+") (pintype "passive"))
    )
    (net (code "59") (name "Net-(BMS11-Pad-)") (class "Default")
      (node (ref "BMS11") (pin "-") (pinfunction "-_-") (pintype "passive"))
      (node (ref "BMS12") (pin "+") (pinfunction "+_+") (pintype "passive"))
    )
    (net (code "60") (name "Net-(BMS12-Pad-)") (class "Default")
      (node (ref "BMS12") (pin "-") (pinfunction "-_-") (pintype "passive"))
      (node (ref "BMS13") (pin "+") (pinfunction "+_+") (pintype "passive"))
    )
    (net (code "61") (name "Net-(BMS13-Pad-)") (class "Default")
      (node (ref "BMS13") (pin "-") (pinfunction "-_-") (pintype "passive"))
      (node (ref "BMS14") (pin "+") (pinfunction "+_+") (pintype "passive"))
    )
    (net (code "62") (name "Net-(BMS14-Pad-)") (class "Default")
      (node (ref "BMS14") (pin "-") (pinfunction "-_-") (pintype "passive"))
      (node (ref "BMS15") (pin "+") (pinfunction "+_+") (pintype "passive"))
    )
    (net (code "63") (name "Net-(BRAKE_LIGHT-C)") (class "Default")
      (node (ref "BRAKE_LIGHT") (pin "K") (pinfunction "C_K") (pintype "passive"))
      (node (ref "JP1") (pin "23") (pinfunction "23_23") (pintype "passive"))
    )
    (net (code "64") (name "Net-(BRAKE_LIGHT-PadA)") (class "Default")
      (node (ref "BRAKE_LIGHT") (pin "A") (pinfunction "A_A") (pintype "passive"))
      (node (ref "JP1") (pin "22") (pinfunction "22_22") (pintype "passive"))
    )
    (net (code "65") (name "Net-(CURRENT-SENSE-Pad1)") (class "Default")
      (node (ref "CURRENT-SENSE") (pin "1") (pinfunction "1_1") (pintype "passive"))
      (node (ref "F1") (pin "1") (pinfunction "1_1") (pintype "passive"))
      (node (ref "SHUNT") (pin "1") (pinfunction "1_1") (pintype "passive"))
    )
    (net (code "66") (name "Net-(CURRENT-SENSE1-Pad1)") (class "Default")
      (node (ref "CURRENT-SENSE1") (pin "1") (pinfunction "1_1") (pintype "passive"))
      (node (ref "F3") (pin "1") (pinfunction "1_1") (pintype "passive"))
      (node (ref "SHUNT1") (pin "1") (pinfunction "1_1") (pintype "passive"))
    )
    (net (code "67") (name "Net-(DDS-Pad2)") (class "Default")
      (node (ref "DDS") (pin "2") (pinfunction "2_2") (pintype "passive"))
      (node (ref "S7") (pin "1") (pinfunction "1_1") (pintype "passive"))
    )
    (net (code "68") (name "Net-(DDS-Pad4)") (class "Default")
      (node (ref "DDS") (pin "4") (pinfunction "4_4") (pintype "passive"))
      (node (ref "S8") (pin "1") (pinfunction "1_1") (pintype "passive"))
    )
    (net (code "69") (name "Net-(DDS-Pad6)") (class "Default")
      (node (ref "DDS") (pin "6") (pinfunction "6_6") (pintype "passive"))
      (node (ref "S9") (pin "1") (pinfunction "1_1") (pintype "passive"))
    )
    (net (code "70") (name "Net-(DDS-Pad8)") (class "Default")
      (node (ref "DDS") (pin "8") (pinfunction "8_8") (pintype "passive"))
      (node (ref "S10") (pin "1") (pinfunction "1_1") (pintype "passive"))
    )
    (net (code "71") (name "Net-(DDS-Pad10)") (class "Default")
      (node (ref "DDS") (pin "10") (pinfunction "10_10") (pintype "passive"))
      (node (ref "S11") (pin "1") (pinfunction "1_1") (pintype "passive"))
    )
    (net (code "72") (name "Net-(DDSB-3)") (class "Default")
      (node (ref "DDS") (pin "15") (pinfunction "3_15") (pintype "passive"))
      (node (ref "R1") (pin "2") (pinfunction "2_2") (pintype "passive"))
    )
    (net (code "73") (name "Net-(DDSB-5)") (class "Default")
      (node (ref "DDS") (pin "17") (pinfunction "5_17") (pintype "passive"))
      (node (ref "R2") (pin "2") (pinfunction "2_2") (pintype "passive"))
    )
    (net (code "74") (name "Net-(DDSB-6)") (class "Default")
      (node (ref "DDS") (pin "18") (pinfunction "6_18") (pintype "passive"))
      (node (ref "IMD") (pin "K") (pinfunction "C_K") (pintype "passive"))
    )
    (net (code "75") (name "Net-(DDSB-7)") (class "Default")
      (node (ref "DDS") (pin "19") (pinfunction "7_19") (pintype "passive"))
      (node (ref "R3") (pin "2") (pinfunction "2_2") (pintype "passive"))
    )
    (net (code "76") (name "Net-(DDSB-8)") (class "Default")
      (node (ref "DDS") (pin "20") (pinfunction "8_20") (pintype "passive"))
      (node (ref "PWS") (pin "K") (pinfunction "C_K") (pintype "passive"))
    )
    (net (code "77") (name "Net-(DDSB-9)") (class "Default")
      (node (ref "DDS") (pin "21") (pinfunction "9_21") (pintype "passive"))
      (node (ref "R4") (pin "2") (pinfunction "2_2") (pintype "passive"))
    )
    (net (code "78") (name "Net-(DDSC-1)") (class "Default")
      (node (ref "DDS") (pin "25") (pinfunction "1_25") (pintype "passive"))
      (node (ref "LED-DISP") (pin "4") (pinfunction "4_4") (pintype "passive"))
    )
    (net (code "79") (name "Net-(DDSC-2)") (class "Default")
      (node (ref "DDS") (pin "26") (pinfunction "2_26") (pintype "passive"))
      (node (ref "LED-DISP") (pin "3") (pinfunction "3_3") (pintype "passive"))
    )
    (net (code "80") (name "Net-(DDSC-3)") (class "Default")
      (node (ref "DDS") (pin "27") (pinfunction "3_27") (pintype "passive"))
      (node (ref "LED-DISP") (pin "2") (pinfunction "2_2") (pintype "passive"))
    )
    (net (code "81") (name "Net-(DDSC-4)") (class "Default")
      (node (ref "DDS") (pin "28") (pinfunction "4_28") (pintype "passive"))
      (node (ref "LED-DISP") (pin "1") (pinfunction "1_1") (pintype "passive"))
    )
    (net (code "82") (name "Net-(DDSC-5)") (class "Default")
      (node (ref "DDS") (pin "29") (pinfunction "5_29") (pintype "passive"))
      (node (ref "S12") (pin "3") (pinfunction "2_3") (pintype "passive"))
    )
    (net (code "83") (name "Net-(DDSC-6)") (class "Default")
      (node (ref "DDS") (pin "30") (pinfunction "6_30") (pintype "passive"))
      (node (ref "S13") (pin "3") (pinfunction "2_3") (pintype "passive"))
    )
    (net (code "84") (name "Net-(DDSC-8)") (class "Default")
      (node (ref "DDS") (pin "32") (pinfunction "8_32") (pintype "passive"))
      (node (ref "S12") (pin "1") (pinfunction "1_1") (pintype "passive"))
      (node (ref "S13") (pin "1") (pinfunction "1_1") (pintype "passive"))
    )
    (net (code "85") (name "Net-(DDSD-1)") (class "Default")
      (node (ref "DDS") (pin "37") (pinfunction "1_37") (pintype "passive"))
      (node (ref "JP1") (pin "18") (pinfunction "18_18") (pintype "passive"))
    )
    (net (code "86") (name "Net-(DDSD-2)") (class "Default")
      (node (ref "DDS") (pin "38") (pinfunction "2_38") (pintype "passive"))
      (node (ref "JP1") (pin "17") (pinfunction "17_17") (pintype "passive"))
    )
    (net (code "87") (name "Net-(DDSD-5)") (class "Default")
      (node (ref "DDS") (pin "41") (pinfunction "5_41") (pintype "passive"))
      (node (ref "JP1") (pin "8") (pinfunction "8_8") (pintype "passive"))
    )
    (net (code "88") (name "Net-(DDSD-6)") (class "Default")
      (node (ref "DDS") (pin "42") (pinfunction "6_42") (pintype "passive"))
      (node (ref "JP1") (pin "7") (pinfunction "7_7") (pintype "passive"))
    )
    (net (code "89") (name "Net-(DDSD-9)") (class "Default")
      (node (ref "DDS") (pin "45") (pinfunction "9_45") (pintype "passive"))
      (node (ref "LCD-DISPLAY") (pin "1") (pinfunction "1_1") (pintype "passive"))
    )
    (net (code "90") (name "Net-(DDSD-10)") (class "Default")
      (node (ref "DDS") (pin "46") (pinfunction "10_46") (pintype "passive"))
      (node (ref "LCD-DISPLAY") (pin "2") (pinfunction "2_2") (pintype "passive"))
    )
    (net (code "91") (name "Net-(DDSD-11)") (class "Default")
      (node (ref "DDS") (pin "47") (pinfunction "11_47") (pintype "passive"))
      (node (ref "LCD-DISPLAY") (pin "3") (pinfunction "3_3") (pintype "passive"))
    )
    (net (code "92") (name "Net-(DDSD-12)") (class "Default")
      (node (ref "DDS") (pin "48") (pinfunction "12_48") (pintype "passive"))
      (node (ref "LCD-DISPLAY") (pin "4") (pinfunction "4_4") (pintype "passive"))
    )
    (net (code "93") (name "Net-(DIS-OUT-Pad1)") (class "Default")
      (node (ref "DIS-OUT") (pin "1") (pinfunction "1_1") (pintype "passive"))
      (node (ref "DISCHAGE1") (pin "2") (pinfunction "2_2") (pintype "passive"))
    )
    (net (code "94") (name "Net-(DIS-OUT1-Pad1)") (class "Default")
      (node (ref "DIS-OUT1") (pin "1") (pinfunction "1_1") (pintype "passive"))
      (node (ref "DISCHAGE3") (pin "2") (pinfunction "2_2") (pintype "passive"))
    )
    (net (code "95") (name "Net-(DISCHAGE1-Pad1)") (class "Default")
      (node (ref "DISCHAGE1") (pin "1") (pinfunction "1_1") (pintype "passive"))
      (node (ref "DISCHAGE2") (pin "2") (pinfunction "2_2") (pintype "passive"))
    )
    (net (code "96") (name "Net-(DISCHAGE3-Pad1)") (class "Default")
      (node (ref "DISCHAGE3") (pin "1") (pinfunction "1_1") (pintype "passive"))
      (node (ref "DISCHAGE4") (pin "2") (pinfunction "2_2") (pintype "passive"))
    )
    (net (code "97") (name "Net-(F5-Pad2)") (class "Default")
      (node (ref "F5") (pin "2") (pinfunction "2_2") (pintype "passive"))
      (node (ref "HV+") (pin "1") (pinfunction "1_1") (pintype "passive"))
    )
    (net (code "98") (name "Net-(F6-Pad2)") (class "Default")
      (node (ref "F6") (pin "2") (pinfunction "2_2") (pintype "passive"))
      (node (ref "PRE-DIS-INPUT") (pin "1") (pinfunction "1_1") (pintype "passive"))
    )
    (net (code "99") (name "Net-(F7-Pad2)") (class "Default")
      (node (ref "F7") (pin "2") (pinfunction "2_2") (pintype "passive"))
      (node (ref "V-SENSE") (pin "1") (pinfunction "1_1") (pintype "passive"))
    )
    (net (code "100") (name "Net-(F8-Pad2)") (class "Default")
      (node (ref "F8") (pin "2") (pinfunction "2_2") (pintype "passive"))
      (node (ref "V-SENSE") (pin "2") (pinfunction "2_2") (pintype "passive"))
    )
    (net (code "101") (name "Net-(F12-Pad2)") (class "Default")
      (node (ref "F12") (pin "2") (pinfunction "2_2") (pintype "passive"))
      (node (ref "PRE-DIS-INPUT1") (pin "1") (pinfunction "1_1") (pintype "passive"))
    )
    (net (code "102") (name "Net-(F13-Pad2)") (class "Default")
      (node (ref "F13") (pin "2") (pinfunction "2_2") (pintype "passive"))
      (node (ref "V-SENSE1") (pin "1") (pinfunction "1_1") (pintype "passive"))
    )
    (net (code "103") (name "Net-(F14-Pad2)") (class "Default")
      (node (ref "F14") (pin "2") (pinfunction "2_2") (pintype "passive"))
      (node (ref "V-SENSE1") (pin "2") (pinfunction "2_2") (pintype "passive"))
    )
    (net (code "104") (name "Net-(G1-Pad+)") (class "Default")
      (node (ref "G1") (pin "+") (pinfunction "+_+") (pintype "passive"))
      (node (ref "S18") (pin "3") (pinfunction "3_3") (pintype "bidirectional"))
      (node (ref "S18") (pin "5") (pinfunction "5_5") (pintype "bidirectional"))
    )
    (net (code "105") (name "Net-(GLVS-O)") (class "Default")
      (node (ref "GLVS") (pin "1") (pinfunction "O_1") (pintype "passive"))
      (node (ref "S18") (pin "2") (pinfunction "2_2") (pintype "bidirectional"))
    )
    (net (code "106") (name "Net-(GLVS-P)") (class "Default")
      (node (ref "GLVS") (pin "2") (pinfunction "P_2") (pintype "passive"))
      (node (ref "JP1") (pin "10") (pinfunction "10_10") (pintype "passive"))
      (node (ref "JP1") (pin "9") (pinfunction "9_9") (pintype "passive"))
    )
    (net (code "107") (name "Net-(IMD-PadA)") (class "Default")
      (node (ref "IMD") (pin "A") (pinfunction "A_A") (pintype "passive"))
      (node (ref "R2") (pin "1") (pinfunction "1_1") (pintype "passive"))
    )
    (net (code "108") (name "Net-(J3-Pad2)") (class "Default")
      (node (ref "J3") (pin "2") (pinfunction "2_2") (pintype "passive"))
      (node (ref "JP15") (pin "9") (pinfunction "9_9") (pintype "passive"))
      (node (ref "JP16") (pin "9") (pinfunction "9_9") (pintype "passive"))
    )
    (net (code "109") (name "Net-(J3-Pad3)") (class "Default")
      (node (ref "J3") (pin "3") (pinfunction "3_3") (pintype "passive"))
      (node (ref "JP15") (pin "10") (pinfunction "10_10") (pintype "passive"))
      (node (ref "JP16") (pin "10") (pinfunction "10_10") (pintype "passive"))
    )
    (net (code "110") (name "Net-(J3-Pad6)") (class "Default")
      (node (ref "J3") (pin "6") (pinfunction "6_6") (pintype "passive"))
      (node (ref "JP16") (pin "8") (pinfunction "8_8") (pintype "passive"))
    )
    (net (code "111") (name "Net-(J3-Pad13)") (class "Default")
      (node (ref "J3") (pin "13") (pinfunction "13_13") (pintype "passive"))
      (node (ref "JP15") (pin "11") (pinfunction "11_11") (pintype "passive"))
    )
    (net (code "112") (name "Net-(JP2-Pad4)") (class "Default")
      (node (ref "JP2") (pin "4") (pinfunction "4_4") (pintype "passive"))
      (node (ref "SP5") (pin "2") (pinfunction "2_2") (pintype "passive"))
    )
    (net (code "113") (name "Net-(JP2-Pad5)") (class "Default")
      (node (ref "JP2") (pin "5") (pinfunction "5_5") (pintype "passive"))
      (node (ref "SP5") (pin "1") (pinfunction "1_1") (pintype "passive"))
    )
    (net (code "114") (name "Net-(JP3-Pad1)") (class "Default")
      (node (ref "JP3") (pin "1") (pinfunction "1_1") (pintype "passive"))
      (node (ref "S18") (pin "4") (pinfunction "4_4") (pintype "bidirectional"))
    )
    (net (code "115") (name "Net-(JP4-Pad1)") (class "Default")
      (node (ref "JP4") (pin "1") (pinfunction "1_1") (pintype "passive"))
      (node (ref "S18") (pin "1") (pinfunction "1_1") (pintype "bidirectional"))
    )
    (net (code "116") (name "Net-(JP5-Pad1)") (class "Default")
      (node (ref "JP5") (pin "1") (pinfunction "1_1") (pintype "passive"))
      (node (ref "R9") (pin "2") (pinfunction "2_2") (pintype "passive"))
    )
    (net (code "117") (name "Net-(JP5-Pad2)") (class "Default")
      (node (ref "JP5") (pin "2") (pinfunction "2_2") (pintype "passive"))
      (node (ref "R8") (pin "2") (pinfunction "2_2") (pintype "passive"))
    )
    (net (code "118") (name "Net-(JP15-Pad8)") (class "Default")
      (node (ref "JP15") (pin "8") (pinfunction "8_8") (pintype "passive"))
      (node (ref "JP16") (pin "7") (pinfunction "7_7") (pintype "passive"))
    )
    (net (code "119") (name "Net-(JP15-Pad13)") (class "Default")
      (node (ref "JP15") (pin "13") (pinfunction "13_13") (pintype "passive"))
      (node (ref "JP16") (pin "13") (pinfunction "13_13") (pintype "passive"))
    )
    (net (code "120") (name "Net-(K1B-P)") (class "Default")
      (node (ref "CURRENT-SENSE") (pin "2") (pinfunction "2_2") (pintype "passive"))
      (node (ref "K1") (pin "COM") (pinfunction "P_COM") (pintype "passive"))
      (node (ref "SHUNT") (pin "2") (pinfunction "2_2") (pintype "passive"))
    )
    (net (code "121") (name "Net-(K2B-P)") (class "Default")
      (node (ref "CURRENT-SENSE1") (pin "2") (pinfunction "2_2") (pintype "passive"))
      (node (ref "K2") (pin "COM") (pinfunction "P_COM") (pintype "passive"))
      (node (ref "SHUNT1") (pin "2") (pinfunction "2_2") (pintype "passive"))
    )
    (net (code "122") (name "Net-(K3B-S)") (class "Default")
      (node (ref "DISCHAGE2") (pin "1") (pinfunction "1_1") (pintype "passive"))
      (node (ref "JP10") (pin "2") (pinfunction "2_2") (pintype "passive"))
      (node (ref "JP7") (pin "1") (pinfunction "1_1") (pintype "passive"))
      (node (ref "K3") (pin "NO") (pinfunction "S_NO") (pintype "passive"))
      (node (ref "R9") (pin "1") (pinfunction "1_1") (pintype "passive"))
    )
    (net (code "123") (name "Net-(K4B-S)") (class "Default")
      (node (ref "DISCHAGE4") (pin "1") (pinfunction "1_1") (pintype "passive"))
      (node (ref "JP9") (pin "1") (pinfunction "1_1") (pintype "passive"))
      (node (ref "K4") (pin "NO") (pinfunction "S_NO") (pintype "passive"))
    )
    (net (code "124") (name "Net-(LED-PWR-IND-Pad2)") (class "Default")
      (node (ref "LED-PWR-IND") (pin "2") (pinfunction "2_2") (pintype "passive"))
      (node (ref "R10") (pin "1") (pinfunction "1_1") (pintype "passive"))
    )
    (net (code "125") (name "Net-(LED-PWR-IND1-Pad2)") (class "Default")
      (node (ref "LED-PWR-IND1") (pin "2") (pinfunction "2_2") (pintype "passive"))
      (node (ref "R11") (pin "1") (pinfunction "1_1") (pintype "passive"))
    )
    (net (code "126") (name "Net-(LED1-C)") (class "Default")
      (node (ref "LED-PWR-IND") (pin "1") (pinfunction "1_1") (pintype "passive"))
      (node (ref "LED1") (pin "K") (pinfunction "C_K") (pintype "passive"))
    )
    (net (code "127") (name "Net-(LED1-PadA)") (class "Default")
      (node (ref "LED1") (pin "A") (pinfunction "A_A") (pintype "passive"))
      (node (ref "R10") (pin "2") (pinfunction "2_2") (pintype "passive"))
    )
    (net (code "128") (name "Net-(LED2-C)") (class "Default")
      (node (ref "LED-PWR-IND1") (pin "1") (pinfunction "1_1") (pintype "passive"))
      (node (ref "LED2") (pin "K") (pinfunction "C_K") (pintype "passive"))
    )
    (net (code "129") (name "Net-(LED2-PadA)") (class "Default")
      (node (ref "LED2") (pin "A") (pinfunction "A_A") (pintype "passive"))
      (node (ref "R11") (pin "2") (pinfunction "2_2") (pintype "passive"))
    )
    (net (code "130") (name "Net-(M1-P$4)") (class "Default")
      (node (ref "J1") (pin "4") (pinfunction "4_4") (pintype "passive"))
      (node (ref "M1") (pin "4") (pinfunction "P$4_4") (pintype "bidirectional"))
    )
    (net (code "131") (name "Net-(M1-P$5)") (class "Default")
      (node (ref "J1") (pin "12") (pinfunction "12_12") (pintype "passive"))
      (node (ref "M1") (pin "5") (pinfunction "P$5_5") (pintype "bidirectional"))
    )
    (net (code "132") (name "Net-(M1-P$6)") (class "Default")
      (node (ref "J1") (pin "11") (pinfunction "11_11") (pintype "passive"))
      (node (ref "M1") (pin "6") (pinfunction "P$6_6") (pintype "bidirectional"))
    )
    (net (code "133") (name "Net-(M1-P$8)") (class "Default")
      (node (ref "J2") (pin "5") (pinfunction "5_5") (pintype "passive"))
      (node (ref "M1") (pin "8") (pinfunction "P$8_8") (pintype "bidirectional"))
    )
    (net (code "134") (name "Net-(M1-P$10)") (class "Default")
      (node (ref "J1") (pin "17") (pinfunction "17_17") (pintype "passive"))
      (node (ref "M1") (pin "10") (pinfunction "P$10_10") (pintype "bidirectional"))
    )
    (net (code "135") (name "Net-(M1-P$11)") (class "Default")
      (node (ref "J1") (pin "3") (pinfunction "3_3") (pintype "passive"))
      (node (ref "M1") (pin "11") (pinfunction "P$11_11") (pintype "bidirectional"))
    )
    (net (code "136") (name "Net-(MCS-Pad4)") (class "Default")
      (node (ref "MCS") (pin "4") (pinfunction "4_4") (pintype "passive"))
      (node (ref "S14") (pin "1") (pinfunction "1_1") (pintype "passive"))
    )
    (net (code "137") (name "Net-(MCS-Pad5)") (class "Default")
      (node (ref "MCS") (pin "5") (pinfunction "5_5") (pintype "passive"))
      (node (ref "S14") (pin "2") (pinfunction "2_2") (pintype "passive"))
    )
    (net (code "138") (name "Net-(MCS-Pad6)") (class "Default")
      (node (ref "MCS") (pin "6") (pinfunction "6_6") (pintype "passive"))
      (node (ref "S15") (pin "2") (pinfunction "2_2") (pintype "passive"))
    )
    (net (code "139") (name "Net-(MCS-Pad7)") (class "Default")
      (node (ref "MCS") (pin "7") (pinfunction "7_7") (pintype "passive"))
      (node (ref "S15") (pin "1") (pinfunction "1_1") (pintype "passive"))
    )
    (net (code "140") (name "Net-(MCS-Pad8)") (class "Default")
      (node (ref "MCS") (pin "8") (pinfunction "8_8") (pintype "passive"))
      (node (ref "S16") (pin "2") (pinfunction "2_2") (pintype "passive"))
    )
    (net (code "141") (name "Net-(MCS-Pad9)") (class "Default")
      (node (ref "MCS") (pin "9") (pinfunction "9_9") (pintype "passive"))
      (node (ref "S16") (pin "1") (pinfunction "1_1") (pintype "passive"))
    )
    (net (code "142") (name "Net-(MCS-Pad10)") (class "Default")
      (node (ref "MCS") (pin "10") (pinfunction "10_10") (pintype "passive"))
      (node (ref "S17") (pin "2") (pinfunction "2_2") (pintype "passive"))
    )
    (net (code "143") (name "Net-(MCS-Pad11)") (class "Default")
      (node (ref "MCS") (pin "11") (pinfunction "11_11") (pintype "passive"))
      (node (ref "S17") (pin "1") (pinfunction "1_1") (pintype "passive"))
    )
    (net (code "144") (name "Net-(MCSC-7)") (class "Default")
      (node (ref "MCS") (pin "31") (pinfunction "7_31") (pintype "passive"))
      (node (ref "R5") (pin "2") (pinfunction "2_2") (pintype "passive"))
    )
    (net (code "145") (name "Net-(MCSC-8)") (class "Default")
      (node (ref "MCS") (pin "32") (pinfunction "8_32") (pintype "passive"))
      (node (ref "R5") (pin "1") (pinfunction "1_1") (pintype "passive"))
    )
    (net (code "146") (name "Net-(MCSC-9)") (class "Default")
      (node (ref "MCS") (pin "33") (pinfunction "9_33") (pintype "passive"))
      (node (ref "R6") (pin "2") (pinfunction "2_2") (pintype "passive"))
    )
    (net (code "147") (name "Net-(MCSC-10)") (class "Default")
      (node (ref "MCS") (pin "34") (pinfunction "10_34") (pintype "passive"))
      (node (ref "R6") (pin "1") (pinfunction "1_1") (pintype "passive"))
    )
    (net (code "148") (name "Net-(MCSC-11)") (class "Default")
      (node (ref "MCS") (pin "35") (pinfunction "11_35") (pintype "passive"))
      (node (ref "R7") (pin "2") (pinfunction "2_2") (pintype "passive"))
    )
    (net (code "149") (name "Net-(MCSC-12)") (class "Default")
      (node (ref "MCS") (pin "36") (pinfunction "12_36") (pintype "passive"))
      (node (ref "R7") (pin "1") (pinfunction "1_1") (pintype "passive"))
    )
    (net (code "150") (name "Net-(MCSD-1)") (class "Default")
      (node (ref "J3") (pin "23") (pinfunction "23_23") (pintype "passive"))
      (node (ref "MCS") (pin "37") (pinfunction "1_37") (pintype "passive"))
    )
    (net (code "151") (name "Net-(MCSD-2)") (class "Default")
      (node (ref "JP1") (pin "16") (pinfunction "16_16") (pintype "passive"))
      (node (ref "MCS") (pin "38") (pinfunction "2_38") (pintype "passive"))
    )
    (net (code "152") (name "Net-(MCSD-3)") (class "Default")
      (node (ref "JP1") (pin "15") (pinfunction "15_15") (pintype "passive"))
      (node (ref "MCS") (pin "39") (pinfunction "3_39") (pintype "passive"))
    )
    (net (code "153") (name "Net-(MCSD-6)") (class "Default")
      (node (ref "JP1") (pin "3") (pinfunction "3_3") (pintype "passive"))
      (node (ref "MCS") (pin "42") (pinfunction "6_42") (pintype "passive"))
    )
    (net (code "154") (name "Net-(MCSD-9)") (class "Default")
      (node (ref "JP1") (pin "4") (pinfunction "4_4") (pintype "passive"))
      (node (ref "MCS") (pin "45") (pinfunction "9_45") (pintype "passive"))
    )
    (net (code "155") (name "Net-(MCSD-11)") (class "Default")
      (node (ref "MCS") (pin "47") (pinfunction "11_47") (pintype "passive"))
      (node (ref "PUMP") (pin "+") (pinfunction "+_+") (pintype "bidirectional"))
    )
    (net (code "156") (name "Net-(MCSD-12)") (class "Default")
      (node (ref "FAN") (pin "+") (pinfunction "+_+") (pintype "bidirectional"))
      (node (ref "MCS") (pin "48") (pinfunction "12_48") (pintype "passive"))
    )
    (net (code "157") (name "Net-(PRE-OUT-Pad1)") (class "Default")
      (node (ref "PRE-OUT") (pin "1") (pinfunction "1_1") (pintype "passive"))
      (node (ref "PRECHARGE1") (pin "2") (pinfunction "2_2") (pintype "passive"))
    )
    (net (code "158") (name "Net-(PRE-OUT1-Pad1)") (class "Default")
      (node (ref "PRE-OUT1") (pin "1") (pinfunction "1_1") (pintype "passive"))
      (node (ref "PRECHARGE3") (pin "2") (pinfunction "2_2") (pintype "passive"))
    )
    (net (code "159") (name "Net-(PRECHARGE-Pad2)") (class "Default")
      (node (ref "PRECHARGE") (pin "2") (pinfunction "2_2") (pintype "passive"))
      (node (ref "PRECHARGE1") (pin "1") (pinfunction "1_1") (pintype "passive"))
    )
    (net (code "160") (name "Net-(PRECHARGE2-Pad2)") (class "Default")
      (node (ref "PRECHARGE2") (pin "2") (pinfunction "2_2") (pintype "passive"))
      (node (ref "PRECHARGE3") (pin "1") (pinfunction "1_1") (pintype "passive"))
    )
    (net (code "161") (name "Net-(PWS-PadA)") (class "Default")
      (node (ref "PWS") (pin "A") (pinfunction "A_A") (pintype "passive"))
      (node (ref "R3") (pin "1") (pinfunction "1_1") (pintype "passive"))
    )
    (net (code "162") (name "Net-(S1-P)") (class "Default")
      (node (ref "S1") (pin "2") (pinfunction "P_2") (pintype "passive"))
      (node (ref "S4") (pin "1") (pinfunction "S_1") (pintype "passive"))
    )
    (net (code "163") (name "Net-(S1-S)") (class "Default")
      (node (ref "S1") (pin "3") (pinfunction "S_3") (pintype "passive"))
      (node (ref "S3") (pin "2") (pinfunction "P_2") (pintype "passive"))
    )
    (net (code "164") (name "Net-(S2A-P)") (class "Default")
      (node (ref "J3") (pin "8") (pinfunction "8_8") (pintype "passive"))
      (node (ref "S2") (pin "2") (pinfunction "P_2") (pintype "passive"))
    )
    (net (code "165") (name "Net-(S2A-S)") (class "Default")
      (node (ref "S2") (pin "1") (pinfunction "S_1") (pintype "passive"))
      (node (ref "S4") (pin "2") (pinfunction "P_2") (pintype "passive"))
    )
    (net (code "166") (name "Net-(S3A-S)") (class "Default")
      (node (ref "S3") (pin "1") (pinfunction "S_1") (pintype "passive"))
      (node (ref "S5") (pin "2") (pinfunction "P_2") (pintype "passive"))
    )
    (net (code "167") (name "Net-(S5A-S)") (class "Default")
      (node (ref "JP15") (pin "7") (pinfunction "7_7") (pintype "passive"))
      (node (ref "S5") (pin "1") (pinfunction "S_1") (pintype "passive"))
    )
    (net (code "168") (name "Net-(S6A-P)") (class "Default")
      (node (ref "J3") (pin "7") (pinfunction "7_7") (pintype "passive"))
      (node (ref "S6") (pin "2") (pinfunction "P_2") (pintype "passive"))
    )
    (net (code "169") (name "Net-(S6A-S)") (class "Default")
      (node (ref "J3") (pin "4") (pinfunction "4_4") (pintype "passive"))
      (node (ref "S6") (pin "1") (pinfunction "S_1") (pintype "passive"))
    )
    (net (code "170") (name "Net-(S7-2)") (class "Default")
      (node (ref "DDS") (pin "1") (pinfunction "1_1") (pintype "passive"))
      (node (ref "S7") (pin "3") (pinfunction "2_3") (pintype "passive"))
    )
    (net (code "171") (name "Net-(S8-2)") (class "Default")
      (node (ref "DDS") (pin "3") (pinfunction "3_3") (pintype "passive"))
      (node (ref "S8") (pin "3") (pinfunction "2_3") (pintype "passive"))
    )
    (net (code "172") (name "Net-(S9-2)") (class "Default")
      (node (ref "DDS") (pin "5") (pinfunction "5_5") (pintype "passive"))
      (node (ref "S9") (pin "3") (pinfunction "2_3") (pintype "passive"))
    )
    (net (code "173") (name "Net-(S10-2)") (class "Default")
      (node (ref "DDS") (pin "7") (pinfunction "7_7") (pintype "passive"))
      (node (ref "S10") (pin "3") (pinfunction "2_3") (pintype "passive"))
    )
    (net (code "174") (name "Net-(S11-2)") (class "Default")
      (node (ref "DDS") (pin "9") (pinfunction "9_9") (pintype "passive"))
      (node (ref "S11") (pin "3") (pinfunction "2_3") (pintype "passive"))
    )
    (net (code "175") (name "Net-(SASB-5)") (class "Default")
      (node (ref "SAS") (pin "17") (pinfunction "5_17") (pintype "passive"))
      (node (ref "SP1") (pin "1") (pinfunction "VCC_1") (pintype "power_in"))
    )
    (net (code "176") (name "Net-(SASB-6)") (class "Default")
      (node (ref "SAS") (pin "18") (pinfunction "6_18") (pintype "passive"))
      (node (ref "SP1") (pin "2") (pinfunction "OUT_2") (pintype "output"))
    )
    (net (code "177") (name "Net-(SASB-7)") (class "Default")
      (node (ref "SAS") (pin "19") (pinfunction "7_19") (pintype "passive"))
      (node (ref "SP1") (pin "3") (pinfunction "GND_3") (pintype "power_in"))
    )
    (net (code "178") (name "Net-(SASB-8)") (class "Default")
      (node (ref "SAS") (pin "20") (pinfunction "8_20") (pintype "passive"))
      (node (ref "SP2") (pin "1") (pinfunction "VCC_1") (pintype "power_in"))
    )
    (net (code "179") (name "Net-(SASB-9)") (class "Default")
      (node (ref "SAS") (pin "21") (pinfunction "9_21") (pintype "passive"))
      (node (ref "SP2") (pin "2") (pinfunction "OUT_2") (pintype "output"))
    )
    (net (code "180") (name "Net-(SASB-10)") (class "Default")
      (node (ref "SAS") (pin "22") (pinfunction "10_22") (pintype "passive"))
      (node (ref "SP2") (pin "3") (pinfunction "GND_3") (pintype "power_in"))
    )
    (net (code "181") (name "Net-(SASB-11)") (class "Default")
      (node (ref "SAS") (pin "23") (pinfunction "11_23") (pintype "passive"))
      (node (ref "SP3") (pin "1") (pinfunction "VCC_1") (pintype "power_in"))
    )
    (net (code "182") (name "Net-(SASB-12)") (class "Default")
      (node (ref "SAS") (pin "24") (pinfunction "12_24") (pintype "passive"))
      (node (ref "SP3") (pin "2") (pinfunction "OUT_2") (pintype "output"))
    )
    (net (code "183") (name "Net-(SASC-1)") (class "Default")
      (node (ref "SAS") (pin "25") (pinfunction "1_25") (pintype "passive"))
      (node (ref "SP3") (pin "3") (pinfunction "GND_3") (pintype "power_in"))
    )
    (net (code "184") (name "Net-(SASC-2)") (class "Default")
      (node (ref "SAS") (pin "26") (pinfunction "2_26") (pintype "passive"))
      (node (ref "SP4") (pin "1") (pinfunction "VCC_1") (pintype "power_in"))
    )
    (net (code "185") (name "Net-(SASC-3)") (class "Default")
      (node (ref "SAS") (pin "27") (pinfunction "3_27") (pintype "passive"))
      (node (ref "SP4") (pin "2") (pinfunction "OUT_2") (pintype "output"))
    )
    (net (code "186") (name "Net-(SASC-4)") (class "Default")
      (node (ref "SAS") (pin "28") (pinfunction "4_28") (pintype "passive"))
      (node (ref "SP4") (pin "3") (pinfunction "GND_3") (pintype "power_in"))
    )
    (net (code "187") (name "Net-(SASD-1)") (class "Default")
      (node (ref "JP1") (pin "20") (pinfunction "20_20") (pintype "passive"))
      (node (ref "SAS") (pin "37") (pinfunction "1_37") (pintype "passive"))
    )
    (net (code "188") (name "Net-(SASD-2)") (class "Default")
      (node (ref "JP1") (pin "5") (pinfunction "5_5") (pintype "passive"))
      (node (ref "SAS") (pin "38") (pinfunction "2_38") (pintype "passive"))
    )
    (net (code "189") (name "Net-(SASD-4)") (class "Default")
      (node (ref "JP1") (pin "19") (pinfunction "19_19") (pintype "passive"))
      (node (ref "SAS") (pin "40") (pinfunction "4_40") (pintype "passive"))
    )
    (net (code "190") (name "Net-(SASD-5)") (class "Default")
      (node (ref "JP1") (pin "6") (pinfunction "6_6") (pintype "passive"))
      (node (ref "SAS") (pin "41") (pinfunction "5_41") (pintype "passive"))
    )
    (net (code "191") (name "Net-(TSS-1D-5)") (class "Default")
      (node (ref "JP1") (pin "28") (pinfunction "28_28") (pintype "passive"))
      (node (ref "TSS-1") (pin "41") (pinfunction "5_41") (pintype "passive"))
    )
    (net (code "192") (name "Net-(TSS-1D-6)") (class "Default")
      (node (ref "JP1") (pin "29") (pinfunction "29_29") (pintype "passive"))
      (node (ref "TSS-1") (pin "42") (pinfunction "6_42") (pintype "passive"))
    )
    (net (code "193") (name "Net-(TSS-1D-7)") (class "Default")
      (node (ref "JP1") (pin "30") (pinfunction "30_30") (pintype "passive"))
      (node (ref "TSS-1") (pin "43") (pinfunction "7_43") (pintype "passive"))
    )
    (net (code "194") (name "Net-(TSS-1D-8)") (class "Default")
      (node (ref "JP2") (pin "1") (pinfunction "1_1") (pintype "passive"))
      (node (ref "TSS-1") (pin "44") (pinfunction "8_44") (pintype "passive"))
    )
    (net (code "195") (name "Net-(TSS-2D-5)") (class "Default")
      (node (ref "JP1") (pin "24") (pinfunction "24_24") (pintype "passive"))
      (node (ref "TSS-2") (pin "41") (pinfunction "5_41") (pintype "passive"))
    )
    (net (code "196") (name "Net-(TSS-2D-6)") (class "Default")
      (node (ref "JP1") (pin "25") (pinfunction "25_25") (pintype "passive"))
      (node (ref "TSS-2") (pin "42") (pinfunction "6_42") (pintype "passive"))
    )
    (net (code "197") (name "Net-(TSS-2D-7)") (class "Default")
      (node (ref "JP1") (pin "26") (pinfunction "26_26") (pintype "passive"))
      (node (ref "TSS-2") (pin "43") (pinfunction "7_43") (pintype "passive"))
    )
    (net (code "198") (name "Net-(TSS-2D-8)") (class "Default")
      (node (ref "JP1") (pin "27") (pinfunction "27_27") (pintype "passive"))
      (node (ref "TSS-2") (pin "44") (pinfunction "8_44") (pintype "passive"))
    )
    (net (code "199") (name "Net-(U$1-HV+)") (class "Default")
      (node (ref "F2") (pin "1") (pinfunction "1_1") (pintype "passive"))
      (node (ref "U$1") (pin "XLA+") (pinfunction "HV+_XLA+") (pintype "bidirectional"))
    )
    (net (code "200") (name "Net-(U$1-HV-)") (class "Default")
      (node (ref "F4") (pin "2") (pinfunction "2_2") (pintype "passive"))
      (node (ref "U$1") (pin "XLA-") (pinfunction "HV-_XLA-") (pintype "bidirectional"))
    )
    (net (code "201") (name "PE") (class "Default")
      (node (ref "FAN") (pin "-") (pinfunction "-_-") (pintype "bidirectional"))
      (node (ref "FAN1") (pin "-") (pinfunction "-_-") (pintype "bidirectional"))
      (node (ref "FAN3") (pin "-") (pinfunction "-_-") (pintype "bidirectional"))
      (node (ref "G1") (pin "-") (pinfunction "-_-") (pintype "passive"))
      (node (ref "J1") (pin "14") (pinfunction "14_14") (pintype "passive"))
      (node (ref "J1") (pin "6") (pinfunction "6_6") (pintype "passive"))
      (node (ref "JP1") (pin "11") (pinfunction "11_11") (pintype "passive"))
      (node (ref "JP1") (pin "12") (pinfunction "12_12") (pintype "passive"))
      (node (ref "JP15") (pin "12") (pinfunction "12_12") (pintype "passive"))
      (node (ref "JP16") (pin "12") (pinfunction "12_12") (pintype "passive"))
      (node (ref "JP3") (pin "2") (pinfunction "2_2") (pintype "passive"))
      (node (ref "JP4") (pin "2") (pinfunction "2_2") (pintype "passive"))
      (node (ref "JP6") (pin "12") (pinfunction "12_12") (pintype "passive"))
      (node (ref "JP8") (pin "12") (pinfunction "12_12") (pintype "passive"))
      (node (ref "K1") (pin "2") (pinfunction "2_2") (pintype "passive"))
      (node (ref "K2") (pin "2") (pinfunction "2_2") (pintype "passive"))
      (node (ref "K3") (pin "2") (pinfunction "2_2") (pintype "passive"))
      (node (ref "K4") (pin "2") (pinfunction "2_2") (pintype "passive"))
      (node (ref "PUMP") (pin "-") (pinfunction "-_-") (pintype "bidirectional"))
      (node (ref "S2") (pin "4") (pinfunction "P_4") (pintype "passive"))
      (node (ref "S3") (pin "4") (pinfunction "P_4") (pintype "passive"))
      (node (ref "S4") (pin "4") (pinfunction "P_4") (pintype "passive"))
      (node (ref "S5") (pin "4") (pinfunction "P_4") (pintype "passive"))
      (node (ref "S6") (pin "4") (pinfunction "P_4") (pintype "passive"))
      (node (ref "U$1") (pin "P$3") (pinfunction "CHASSISGND_P$3") (pintype "bidirectional"))
      (node (ref "U$1") (pin "P$4") (pinfunction "CHASSISGND_P$4") (pintype "bidirectional"))
    )
    (net (code "202") (name "unconnected-(BMM-Pad1)") (class "Default")
      (node (ref "BMM") (pin "1") (pinfunction "1_1") (pintype "passive"))
    )
    (net (code "203") (name "unconnected-(BMM-Pad2)") (class "Default")
      (node (ref "BMM") (pin "2") (pinfunction "2_2") (pintype "passive"))
    )
    (net (code "204") (name "unconnected-(BMM-Pad3)") (class "Default")
      (node (ref "BMM") (pin "3") (pinfunction "3_3") (pintype "passive"))
    )
    (net (code "205") (name "unconnected-(BMM-Pad4)") (class "Default")
      (node (ref "BMM") (pin "4") (pinfunction "4_4") (pintype "passive"))
    )
    (net (code "206") (name "unconnected-(BMM-Pad5)") (class "Default")
      (node (ref "BMM") (pin "5") (pinfunction "5_5") (pintype "passive"))
    )
    (net (code "207") (name "unconnected-(BMM-Pad6)") (class "Default")
      (node (ref "BMM") (pin "6") (pinfunction "6_6") (pintype "passive"))
    )
    (net (code "208") (name "unconnected-(BMM-Pad7)") (class "Default")
      (node (ref "BMM") (pin "7") (pinfunction "7_7") (pintype "passive"))
    )
    (net (code "209") (name "unconnected-(BMM-Pad8)") (class "Default")
      (node (ref "BMM") (pin "8") (pinfunction "8_8") (pintype "passive"))
    )
    (net (code "210") (name "unconnected-(BMM-Pad9)") (class "Default")
      (node (ref "BMM") (pin "9") (pinfunction "9_9") (pintype "passive"))
    )
    (net (code "211") (name "unconnected-(BMM-Pad10)") (class "Default")
      (node (ref "BMM") (pin "10") (pinfunction "10_10") (pintype "passive"))
    )
    (net (code "212") (name "unconnected-(BMM-Pad11)") (class "Default")
      (node (ref "BMM") (pin "11") (pinfunction "11_11") (pintype "passive"))
    )
    (net (code "213") (name "unconnected-(BMM-Pad12)") (class "Default")
      (node (ref "BMM") (pin "12") (pinfunction "12_12") (pintype "passive"))
    )
    (net (code "214") (name "unconnected-(BMMB-1-Pad13)") (class "Default")
      (node (ref "BMM") (pin "13") (pinfunction "1_13") (pintype "passive"))
    )
    (net (code "215") (name "unconnected-(BMMB-2-Pad14)") (class "Default")
      (node (ref "BMM") (pin "14") (pinfunction "2_14") (pintype "passive"))
    )
    (net (code "216") (name "unconnected-(BMMB-3-Pad15)") (class "Default")
      (node (ref "BMM") (pin "15") (pinfunction "3_15") (pintype "passive"))
    )
    (net (code "217") (name "unconnected-(BMMB-4-Pad16)") (class "Default")
      (node (ref "BMM") (pin "16") (pinfunction "4_16") (pintype "passive"))
    )
    (net (code "218") (name "unconnected-(BMMB-5-Pad17)") (class "Default")
      (node (ref "BMM") (pin "17") (pinfunction "5_17") (pintype "passive"))
    )
    (net (code "219") (name "unconnected-(BMMB-6-Pad18)") (class "Default")
      (node (ref "BMM") (pin "18") (pinfunction "6_18") (pintype "passive"))
    )
    (net (code "220") (name "unconnected-(BMMB-7-Pad19)") (class "Default")
      (node (ref "BMM") (pin "19") (pinfunction "7_19") (pintype "passive"))
    )
    (net (code "221") (name "unconnected-(BMMB-8-Pad20)") (class "Default")
      (node (ref "BMM") (pin "20") (pinfunction "8_20") (pintype "passive"))
    )
    (net (code "222") (name "unconnected-(BMMB-9-Pad21)") (class "Default")
      (node (ref "BMM") (pin "21") (pinfunction "9_21") (pintype "passive"))
    )
    (net (code "223") (name "unconnected-(BMMB-10-Pad22)") (class "Default")
      (node (ref "BMM") (pin "22") (pinfunction "10_22") (pintype "passive"))
    )
    (net (code "224") (name "unconnected-(BMMB-11-Pad23)") (class "Default")
      (node (ref "BMM") (pin "23") (pinfunction "11_23") (pintype "passive"))
    )
    (net (code "225") (name "unconnected-(BMMB-12-Pad24)") (class "Default")
      (node (ref "BMM") (pin "24") (pinfunction "12_24") (pintype "passive"))
    )
    (net (code "226") (name "unconnected-(BMMC-1-Pad25)") (class "Default")
      (node (ref "BMM") (pin "25") (pinfunction "1_25") (pintype "passive"))
    )
    (net (code "227") (name "unconnected-(BMMC-2-Pad26)") (class "Default")
      (node (ref "BMM") (pin "26") (pinfunction "2_26") (pintype "passive"))
    )
    (net (code "228") (name "unconnected-(BMMC-3-Pad27)") (class "Default")
      (node (ref "BMM") (pin "27") (pinfunction "3_27") (pintype "passive"))
    )
    (net (code "229") (name "unconnected-(BMMC-4-Pad28)") (class "Default")
      (node (ref "BMM") (pin "28") (pinfunction "4_28") (pintype "passive"))
    )
    (net (code "230") (name "unconnected-(BMMC-5-Pad29)") (class "Default")
      (node (ref "BMM") (pin "29") (pinfunction "5_29") (pintype "passive"))
    )
    (net (code "231") (name "unconnected-(BMMC-6-Pad30)") (class "Default")
      (node (ref "BMM") (pin "30") (pinfunction "6_30") (pintype "passive"))
    )
    (net (code "232") (name "unconnected-(BMMC-7-Pad31)") (class "Default")
      (node (ref "BMM") (pin "31") (pinfunction "7_31") (pintype "passive"))
    )
    (net (code "233") (name "unconnected-(BMMC-8-Pad32)") (class "Default")
      (node (ref "BMM") (pin "32") (pinfunction "8_32") (pintype "passive"))
    )
    (net (code "234") (name "unconnected-(BMMC-9-Pad33)") (class "Default")
      (node (ref "BMM") (pin "33") (pinfunction "9_33") (pintype "passive"))
    )
    (net (code "235") (name "unconnected-(BMMC-12-Pad36)") (class "Default")
      (node (ref "BMM") (pin "36") (pinfunction "12_36") (pintype "passive"))
    )
    (net (code "236") (name "unconnected-(BMMD-1-Pad37)") (class "Default")
      (node (ref "BMM") (pin "37") (pinfunction "1_37") (pintype "passive"))
    )
    (net (code "237") (name "unconnected-(BMMD-2-Pad38)") (class "Default")
      (node (ref "BMM") (pin "38") (pinfunction "2_38") (pintype "passive"))
    )
    (net (code "238") (name "unconnected-(BMMD-3-Pad39)") (class "Default")
      (node (ref "BMM") (pin "39") (pinfunction "3_39") (pintype "passive"))
    )
    (net (code "239") (name "unconnected-(BMMD-6-Pad42)") (class "Default")
      (node (ref "BMM") (pin "42") (pinfunction "6_42") (pintype "passive"))
    )
    (net (code "240") (name "unconnected-(BMMD-7-Pad43)") (class "Default")
      (node (ref "BMM") (pin "43") (pinfunction "7_43") (pintype "passive"))
    )
    (net (code "241") (name "unconnected-(BMMD-8-Pad44)") (class "Default")
      (node (ref "BMM") (pin "44") (pinfunction "8_44") (pintype "passive"))
    )
    (net (code "242") (name "unconnected-(BMMD-9-Pad45)") (class "Default")
      (node (ref "BMM") (pin "45") (pinfunction "9_45") (pintype "passive"))
    )
    (net (code "243") (name "unconnected-(BMMD-10-Pad46)") (class "Default")
      (node (ref "BMM") (pin "46") (pinfunction "10_46") (pintype "passive"))
    )
    (net (code "244") (name "unconnected-(BMMD-11-Pad47)") (class "Default")
      (node (ref "BMM") (pin "47") (pinfunction "11_47") (pintype "passive"))
    )
    (net (code "245") (name "unconnected-(BMMD-12-Pad48)") (class "Default")
      (node (ref "BMM") (pin "48") (pinfunction "12_48") (pintype "passive"))
    )
    (net (code "246") (name "unconnected-(BMS1-+-Pad+@1)") (class "Default")
      (node (ref "BMS1") (pin "+@1") (pinfunction "+_+@1") (pintype "passive"))
    )
    (net (code "247") (name "unconnected-(BMS2-+-Pad+@1)") (class "Default")
      (node (ref "BMS2") (pin "+@1") (pinfunction "+_+@1") (pintype "passive"))
    )
    (net (code "248") (name "unconnected-(BMS3-+-Pad+@1)") (class "Default")
      (node (ref "BMS3") (pin "+@1") (pinfunction "+_+@1") (pintype "passive"))
    )
    (net (code "249") (name "unconnected-(BMS4-+-Pad+@1)") (class "Default")
      (node (ref "BMS4") (pin "+@1") (pinfunction "+_+@1") (pintype "passive"))
    )
    (net (code "250") (name "unconnected-(BMS5-+-Pad+@1)") (class "Default")
      (node (ref "BMS5") (pin "+@1") (pinfunction "+_+@1") (pintype "passive"))
    )
    (net (code "251") (name "unconnected-(BMS6-+-Pad+@1)") (class "Default")
      (node (ref "BMS6") (pin "+@1") (pinfunction "+_+@1") (pintype "passive"))
    )
    (net (code "252") (name "unconnected-(BMS7-+-Pad+@1)") (class "Default")
      (node (ref "BMS7") (pin "+@1") (pinfunction "+_+@1") (pintype "passive"))
    )
    (net (code "253") (name "unconnected-(BMS8-Pad1)") (class "Default")
      (node (ref "BMS8") (pin "1") (pinfunction "1_1") (pintype "passive"))
    )
    (net (code "254") (name "unconnected-(BMS8-Pad2)") (class "Default")
      (node (ref "BMS8") (pin "2") (pinfunction "2_2") (pintype "passive"))
    )
    (net (code "255") (name "unconnected-(BMS8-Pad3)") (class "Default")
      (node (ref "BMS8") (pin "3") (pinfunction "3_3") (pintype "passive"))
    )
    (net (code "256") (name "unconnected-(BMS8-Pad4)") (class "Default")
      (node (ref "BMS8") (pin "4") (pinfunction "4_4") (pintype "passive"))
    )
    (net (code "257") (name "unconnected-(BMS9-+-Pad+@1)") (class "Default")
      (node (ref "BMS9") (pin "+@1") (pinfunction "+_+@1") (pintype "passive"))
    )
    (net (code "258") (name "unconnected-(BMS10-+-Pad+@1)") (class "Default")
      (node (ref "BMS10") (pin "+@1") (pinfunction "+_+@1") (pintype "passive"))
    )
    (net (code "259") (name "unconnected-(BMS11-+-Pad+@1)") (class "Default")
      (node (ref "BMS11") (pin "+@1") (pinfunction "+_+@1") (pintype "passive"))
    )
    (net (code "260") (name "unconnected-(BMS12-+-Pad+@1)") (class "Default")
      (node (ref "BMS12") (pin "+@1") (pinfunction "+_+@1") (pintype "passive"))
    )
    (net (code "261") (name "unconnected-(BMS13-+-Pad+@1)") (class "Default")
      (node (ref "BMS13") (pin "+@1") (pinfunction "+_+@1") (pintype "passive"))
    )
    (net (code "262") (name "unconnected-(BMS14-+-Pad+@1)") (class "Default")
      (node (ref "BMS14") (pin "+@1") (pinfunction "+_+@1") (pintype "passive"))
    )
    (net (code "263") (name "unconnected-(BMS15-+-Pad+@1)") (class "Default")
      (node (ref "BMS15") (pin "+@1") (pinfunction "+_+@1") (pintype "passive"))
    )
    (net (code "264") (name "unconnected-(BMS16-Pad1)") (class "Default")
      (node (ref "BMS16") (pin "1") (pinfunction "1_1") (pintype "passive"))
    )
    (net (code "265") (name "unconnected-(BMS16-Pad2)") (class "Default")
      (node (ref "BMS16") (pin "2") (pinfunction "2_2") (pintype "passive"))
    )
    (net (code "266") (name "unconnected-(BMS16-Pad3)") (class "Default")
      (node (ref "BMS16") (pin "3") (pinfunction "3_3") (pintype "passive"))
    )
    (net (code "267") (name "unconnected-(BMS16-Pad4)") (class "Default")
      (node (ref "BMS16") (pin "4") (pinfunction "4_4") (pintype "passive"))
    )
    (net (code "268") (name "unconnected-(DDS-Pad11)") (class "Default")
      (node (ref "DDS") (pin "11") (pinfunction "11_11") (pintype "passive"))
    )
    (net (code "269") (name "unconnected-(DDS-Pad12)") (class "Default")
      (node (ref "DDS") (pin "12") (pinfunction "12_12") (pintype "passive"))
    )
    (net (code "270") (name "unconnected-(DDSB-1-Pad13)") (class "Default")
      (node (ref "DDS") (pin "13") (pinfunction "1_13") (pintype "passive"))
    )
    (net (code "271") (name "unconnected-(DDSB-2-Pad14)") (class "Default")
      (node (ref "DDS") (pin "14") (pinfunction "2_14") (pintype "passive"))
    )
    (net (code "272") (name "unconnected-(DDSB-11-Pad23)") (class "Default")
      (node (ref "DDS") (pin "23") (pinfunction "11_23") (pintype "passive"))
    )
    (net (code "273") (name "unconnected-(DDSB-12-Pad24)") (class "Default")
      (node (ref "DDS") (pin "24") (pinfunction "12_24") (pintype "passive"))
    )
    (net (code "274") (name "unconnected-(DDSC-7-Pad31)") (class "Default")
      (node (ref "DDS") (pin "31") (pinfunction "7_31") (pintype "passive"))
    )
    (net (code "275") (name "unconnected-(DDSC-9-Pad33)") (class "Default")
      (node (ref "DDS") (pin "33") (pinfunction "9_33") (pintype "passive"))
    )
    (net (code "276") (name "unconnected-(DDSC-10-Pad34)") (class "Default")
      (node (ref "DDS") (pin "34") (pinfunction "10_34") (pintype "passive"))
    )
    (net (code "277") (name "unconnected-(DDSC-11-Pad35)") (class "Default")
      (node (ref "DDS") (pin "35") (pinfunction "11_35") (pintype "passive"))
    )
    (net (code "278") (name "unconnected-(DDSC-12-Pad36)") (class "Default")
      (node (ref "DDS") (pin "36") (pinfunction "12_36") (pintype "passive"))
    )
    (net (code "279") (name "unconnected-(DDSD-3-Pad39)") (class "Default")
      (node (ref "DDS") (pin "39") (pinfunction "3_39") (pintype "passive"))
    )
    (net (code "280") (name "unconnected-(DDSD-4-Pad40)") (class "Default")
      (node (ref "DDS") (pin "40") (pinfunction "4_40") (pintype "passive"))
    )
    (net (code "281") (name "unconnected-(DDSD-7-Pad43)") (class "Default")
      (node (ref "DDS") (pin "43") (pinfunction "7_43") (pintype "passive"))
    )
    (net (code "282") (name "unconnected-(DDSD-8-Pad44)") (class "Default")
      (node (ref "DDS") (pin "44") (pinfunction "8_44") (pintype "passive"))
    )
    (net (code "283") (name "unconnected-(J1-Pad1)") (class "Default")
      (node (ref "J1") (pin "1") (pinfunction "1_1") (pintype "passive"))
    )
    (net (code "284") (name "unconnected-(J1-Pad2)") (class "Default")
      (node (ref "J1") (pin "2") (pinfunction "2_2") (pintype "passive"))
    )
    (net (code "285") (name "unconnected-(J1-Pad5)") (class "Default")
      (node (ref "J1") (pin "5") (pinfunction "5_5") (pintype "passive"))
    )
    (net (code "286") (name "unconnected-(J1-Pad7)") (class "Default")
      (node (ref "J1") (pin "7") (pinfunction "7_7") (pintype "passive"))
    )
    (net (code "287") (name "unconnected-(J1-Pad9)") (class "Default")
      (node (ref "J1") (pin "9") (pinfunction "9_9") (pintype "passive"))
    )
    (net (code "288") (name "unconnected-(J1-Pad10)") (class "Default")
      (node (ref "J1") (pin "10") (pinfunction "10_10") (pintype "passive"))
    )
    (net (code "289") (name "unconnected-(J1-Pad13)") (class "Default")
      (node (ref "J1") (pin "13") (pinfunction "13_13") (pintype "passive"))
    )
    (net (code "290") (name "unconnected-(J1-Pad15)") (class "Default")
      (node (ref "J1") (pin "15") (pinfunction "15_15") (pintype "passive"))
    )
    (net (code "291") (name "unconnected-(J1-Pad16)") (class "Default")
      (node (ref "J1") (pin "16") (pinfunction "16_16") (pintype "passive"))
    )
    (net (code "292") (name "unconnected-(J1-Pad18)") (class "Default")
      (node (ref "J1") (pin "18") (pinfunction "18_18") (pintype "passive"))
    )
    (net (code "293") (name "unconnected-(J1-Pad19)") (class "Default")
      (node (ref "J1") (pin "19") (pinfunction "19_19") (pintype "passive"))
    )
    (net (code "294") (name "unconnected-(J1-Pad20)") (class "Default")
      (node (ref "J1") (pin "20") (pinfunction "20_20") (pintype "passive"))
    )
    (net (code "295") (name "unconnected-(J1-Pad21)") (class "Default")
      (node (ref "J1") (pin "21") (pinfunction "21_21") (pintype "passive"))
    )
    (net (code "296") (name "unconnected-(J1-Pad22)") (class "Default")
      (node (ref "J1") (pin "22") (pinfunction "22_22") (pintype "passive"))
    )
    (net (code "297") (name "unconnected-(J2-Pad1)") (class "Default")
      (node (ref "J2") (pin "1") (pinfunction "1_1") (pintype "passive"))
    )
    (net (code "298") (name "unconnected-(J2-Pad3)") (class "Default")
      (node (ref "J2") (pin "3") (pinfunction "3_3") (pintype "passive"))
    )
    (net (code "299") (name "unconnected-(J2-Pad4)") (class "Default")
      (node (ref "J2") (pin "4") (pinfunction "4_4") (pintype "passive"))
    )
    (net (code "300") (name "unconnected-(J2-Pad6)") (class "Default")
      (node (ref "J2") (pin "6") (pinfunction "6_6") (pintype "passive"))
    )
    (net (code "301") (name "unconnected-(J2-Pad9)") (class "Default")
      (node (ref "J2") (pin "9") (pinfunction "9_9") (pintype "passive"))
    )
    (net (code "302") (name "unconnected-(J2-Pad10)") (class "Default")
      (node (ref "J2") (pin "10") (pinfunction "10_10") (pintype "passive"))
    )
    (net (code "303") (name "unconnected-(J2-Pad11)") (class "Default")
      (node (ref "J2") (pin "11") (pinfunction "11_11") (pintype "passive"))
    )
    (net (code "304") (name "unconnected-(J2-Pad14)") (class "Default")
      (node (ref "J2") (pin "14") (pinfunction "14_14") (pintype "passive"))
    )
    (net (code "305") (name "unconnected-(J2-Pad15)") (class "Default")
      (node (ref "J2") (pin "15") (pinfunction "15_15") (pintype "passive"))
    )
    (net (code "306") (name "unconnected-(J2-Pad16)") (class "Default")
      (node (ref "J2") (pin "16") (pinfunction "16_16") (pintype "passive"))
    )
    (net (code "307") (name "unconnected-(J2-Pad17)") (class "Default")
      (node (ref "J2") (pin "17") (pinfunction "17_17") (pintype "passive"))
    )
    (net (code "308") (name "unconnected-(J2-Pad18)") (class "Default")
      (node (ref "J2") (pin "18") (pinfunction "18_18") (pintype "passive"))
    )
    (net (code "309") (name "unconnected-(J2-Pad19)") (class "Default")
      (node (ref "J2") (pin "19") (pinfunction "19_19") (pintype "passive"))
    )
    (net (code "310") (name "unconnected-(J2-Pad21)") (class "Default")
      (node (ref "J2") (pin "21") (pinfunction "21_21") (pintype "passive"))
    )
    (net (code "311") (name "unconnected-(J2-Pad22)") (class "Default")
      (node (ref "J2") (pin "22") (pinfunction "22_22") (pintype "passive"))
    )
    (net (code "312") (name "unconnected-(J2-Pad23)") (class "Default")
      (node (ref "J2") (pin "23") (pinfunction "23_23") (pintype "passive"))
    )
    (net (code "313") (name "unconnected-(J2-Pad24)") (class "Default")
      (node (ref "J2") (pin "24") (pinfunction "24_24") (pintype "passive"))
    )
    (net (code "314") (name "unconnected-(J2-Pad26)") (class "Default")
      (node (ref "J2") (pin "26") (pinfunction "26_26") (pintype "passive"))
    )
    (net (code "315") (name "unconnected-(J2-Pad27)") (class "Default")
      (node (ref "J2") (pin "27") (pinfunction "27_27") (pintype "passive"))
    )
    (net (code "316") (name "unconnected-(J2-Pad28)") (class "Default")
      (node (ref "J2") (pin "28") (pinfunction "28_28") (pintype "passive"))
    )
    (net (code "317") (name "unconnected-(J2-Pad29)") (class "Default")
      (node (ref "J2") (pin "29") (pinfunction "29_29") (pintype "passive"))
    )
    (net (code "318") (name "unconnected-(J2-Pad32)") (class "Default")
      (node (ref "J2") (pin "32") (pinfunction "32_32") (pintype "passive"))
    )
    (net (code "319") (name "unconnected-(J2-Pad33)") (class "Default")
      (node (ref "J2") (pin "33") (pinfunction "33_33") (pintype "passive"))
    )
    (net (code "320") (name "unconnected-(J2-Pad34)") (class "Default")
      (node (ref "J2") (pin "34") (pinfunction "34_34") (pintype "passive"))
    )
    (net (code "321") (name "unconnected-(J3-Pad1)") (class "Default")
      (node (ref "J3") (pin "1") (pinfunction "1_1") (pintype "passive"))
    )
    (net (code "322") (name "unconnected-(J3-Pad5)") (class "Default")
      (node (ref "J3") (pin "5") (pinfunction "5_5") (pintype "passive"))
    )
    (net (code "323") (name "unconnected-(J3-Pad12)") (class "Default")
      (node (ref "J3") (pin "12") (pinfunction "12_12") (pintype "passive"))
    )
    (net (code "324") (name "unconnected-(J3-Pad14)") (class "Default")
      (node (ref "J3") (pin "14") (pinfunction "14_14") (pintype "passive"))
    )
    (net (code "325") (name "unconnected-(J3-Pad15)") (class "Default")
      (node (ref "J3") (pin "15") (pinfunction "15_15") (pintype "passive"))
    )
    (net (code "326") (name "unconnected-(J3-Pad19)") (class "Default")
      (node (ref "J3") (pin "19") (pinfunction "19_19") (pintype "passive"))
    )
    (net (code "327") (name "unconnected-(J3-Pad20)") (class "Default")
      (node (ref "J3") (pin "20") (pinfunction "20_20") (pintype "passive"))
    )
    (net (code "328") (name "unconnected-(J3-Pad21)") (class "Default")
      (node (ref "J3") (pin "21") (pinfunction "21_21") (pintype "passive"))
    )
    (net (code "329") (name "unconnected-(J3-Pad22)") (class "Default")
      (node (ref "J3") (pin "22") (pinfunction "22_22") (pintype "passive"))
    )
    (net (code "330") (name "unconnected-(JP1-Pad21)") (class "Default")
      (node (ref "JP1") (pin "21") (pinfunction "21_21") (pintype "passive"))
    )
    (net (code "331") (name "unconnected-(JP2-Pad2)") (class "Default")
      (node (ref "JP2") (pin "2") (pinfunction "2_2") (pintype "passive"))
    )
    (net (code "332") (name "unconnected-(JP2-Pad3)") (class "Default")
      (node (ref "JP2") (pin "3") (pinfunction "3_3") (pintype "passive"))
    )
    (net (code "333") (name "unconnected-(JP6-Pad3)") (class "Default")
      (node (ref "JP6") (pin "3") (pinfunction "3_3") (pintype "passive"))
    )
    (net (code "334") (name "unconnected-(JP6-Pad4)") (class "Default")
      (node (ref "JP6") (pin "4") (pinfunction "4_4") (pintype "passive"))
    )
    (net (code "335") (name "unconnected-(JP6-Pad5)") (class "Default")
      (node (ref "JP6") (pin "5") (pinfunction "5_5") (pintype "passive"))
    )
    (net (code "336") (name "unconnected-(JP6-Pad6)") (class "Default")
      (node (ref "JP6") (pin "6") (pinfunction "6_6") (pintype "passive"))
    )
    (net (code "337") (name "unconnected-(JP6-Pad7)") (class "Default")
      (node (ref "JP6") (pin "7") (pinfunction "7_7") (pintype "passive"))
    )
    (net (code "338") (name "unconnected-(JP6-Pad8)") (class "Default")
      (node (ref "JP6") (pin "8") (pinfunction "8_8") (pintype "passive"))
    )
    (net (code "339") (name "unconnected-(JP6-Pad13)") (class "Default")
      (node (ref "JP6") (pin "13") (pinfunction "13_13") (pintype "passive"))
    )
    (net (code "340") (name "unconnected-(JP6-Pad14)") (class "Default")
      (node (ref "JP6") (pin "14") (pinfunction "14_14") (pintype "passive"))
    )
    (net (code "341") (name "unconnected-(JP6-Pad15)") (class "Default")
      (node (ref "JP6") (pin "15") (pinfunction "15_15") (pintype "passive"))
    )
    (net (code "342") (name "unconnected-(JP6-Pad16)") (class "Default")
      (node (ref "JP6") (pin "16") (pinfunction "16_16") (pintype "passive"))
    )
    (net (code "343") (name "unconnected-(JP6-Pad17)") (class "Default")
      (node (ref "JP6") (pin "17") (pinfunction "17_17") (pintype "passive"))
    )
    (net (code "344") (name "unconnected-(JP6-Pad18)") (class "Default")
      (node (ref "JP6") (pin "18") (pinfunction "18_18") (pintype "passive"))
    )
    (net (code "345") (name "unconnected-(JP6-Pad19)") (class "Default")
      (node (ref "JP6") (pin "19") (pinfunction "19_19") (pintype "passive"))
    )
    (net (code "346") (name "unconnected-(JP6-Pad20)") (class "Default")
      (node (ref "JP6") (pin "20") (pinfunction "20_20") (pintype "passive"))
    )
    (net (code "347") (name "unconnected-(JP8-Pad5)") (class "Default")
      (node (ref "JP8") (pin "5") (pinfunction "5_5") (pintype "passive"))
    )
    (net (code "348") (name "unconnected-(JP8-Pad6)") (class "Default")
      (node (ref "JP8") (pin "6") (pinfunction "6_6") (pintype "passive"))
    )
    (net (code "349") (name "unconnected-(JP8-Pad13)") (class "Default")
      (node (ref "JP8") (pin "13") (pinfunction "13_13") (pintype "passive"))
    )
    (net (code "350") (name "unconnected-(JP8-Pad14)") (class "Default")
      (node (ref "JP8") (pin "14") (pinfunction "14_14") (pintype "passive"))
    )
    (net (code "351") (name "unconnected-(JP8-Pad15)") (class "Default")
      (node (ref "JP8") (pin "15") (pinfunction "15_15") (pintype "passive"))
    )
    (net (code "352") (name "unconnected-(JP8-Pad16)") (class "Default")
      (node (ref "JP8") (pin "16") (pinfunction "16_16") (pintype "passive"))
    )
    (net (code "353") (name "unconnected-(JP8-Pad17)") (class "Default")
      (node (ref "JP8") (pin "17") (pinfunction "17_17") (pintype "passive"))
    )
    (net (code "354") (name "unconnected-(JP8-Pad18)") (class "Default")
      (node (ref "JP8") (pin "18") (pinfunction "18_18") (pintype "passive"))
    )
    (net (code "355") (name "unconnected-(JP8-Pad19)") (class "Default")
      (node (ref "JP8") (pin "19") (pinfunction "19_19") (pintype "passive"))
    )
    (net (code "356") (name "unconnected-(JP8-Pad20)") (class "Default")
      (node (ref "JP8") (pin "20") (pinfunction "20_20") (pintype "passive"))
    )
    (net (code "357") (name "unconnected-(JP11-Pad1)") (class "Default")
      (node (ref "JP11") (pin "1") (pinfunction "1_1") (pintype "passive"))
    )
    (net (code "358") (name "unconnected-(JP11-Pad2)") (class "Default")
      (node (ref "JP11") (pin "2") (pinfunction "2_2") (pintype "passive"))
    )
    (net (code "359") (name "unconnected-(JP12-Pad1)") (class "Default")
      (node (ref "JP12") (pin "1") (pinfunction "1_1") (pintype "passive"))
    )
    (net (code "360") (name "unconnected-(JP12-Pad2)") (class "Default")
      (node (ref "JP12") (pin "2") (pinfunction "2_2") (pintype "passive"))
    )
    (net (code "361") (name "unconnected-(JP13-Pad1)") (class "Default")
      (node (ref "JP13") (pin "1") (pinfunction "1_1") (pintype "passive"))
    )
    (net (code "362") (name "unconnected-(JP13-Pad2)") (class "Default")
      (node (ref "JP13") (pin "2") (pinfunction "2_2") (pintype "passive"))
    )
    (net (code "363") (name "unconnected-(JP14-Pad1)") (class "Default")
      (node (ref "JP14") (pin "1") (pinfunction "1_1") (pintype "passive"))
    )
    (net (code "364") (name "unconnected-(JP14-Pad2)") (class "Default")
      (node (ref "JP14") (pin "2") (pinfunction "2_2") (pintype "passive"))
    )
    (net (code "365") (name "unconnected-(JP15-Pad1)") (class "Default")
      (node (ref "JP15") (pin "1") (pinfunction "1_1") (pintype "passive"))
    )
    (net (code "366") (name "unconnected-(JP15-Pad2)") (class "Default")
      (node (ref "JP15") (pin "2") (pinfunction "2_2") (pintype "passive"))
    )
    (net (code "367") (name "unconnected-(JP15-Pad3)") (class "Default")
      (node (ref "JP15") (pin "3") (pinfunction "3_3") (pintype "passive"))
    )
    (net (code "368") (name "unconnected-(JP15-Pad4)") (class "Default")
      (node (ref "JP15") (pin "4") (pinfunction "4_4") (pintype "passive"))
    )
    (net (code "369") (name "unconnected-(JP15-Pad5)") (class "Default")
      (node (ref "JP15") (pin "5") (pinfunction "5_5") (pintype "passive"))
    )
    (net (code "370") (name "unconnected-(JP15-Pad6)") (class "Default")
      (node (ref "JP15") (pin "6") (pinfunction "6_6") (pintype "passive"))
    )
    (net (code "371") (name "unconnected-(JP15-Pad15)") (class "Default")
      (node (ref "JP15") (pin "15") (pinfunction "15_15") (pintype "passive"))
    )
    (net (code "372") (name "unconnected-(JP15-Pad16)") (class "Default")
      (node (ref "JP15") (pin "16") (pinfunction "16_16") (pintype "passive"))
    )
    (net (code "373") (name "unconnected-(JP15-Pad17)") (class "Default")
      (node (ref "JP15") (pin "17") (pinfunction "17_17") (pintype "passive"))
    )
    (net (code "374") (name "unconnected-(JP15-Pad18)") (class "Default")
      (node (ref "JP15") (pin "18") (pinfunction "18_18") (pintype "passive"))
    )
    (net (code "375") (name "unconnected-(JP15-Pad19)") (class "Default")
      (node (ref "JP15") (pin "19") (pinfunction "19_19") (pintype "passive"))
    )
    (net (code "376") (name "unconnected-(JP15-Pad20)") (class "Default")
      (node (ref "JP15") (pin "20") (pinfunction "20_20") (pintype "passive"))
    )
    (net (code "377") (name "unconnected-(JP16-Pad1)") (class "Default")
      (node (ref "JP16") (pin "1") (pinfunction "1_1") (pintype "passive"))
    )
    (net (code "378") (name "unconnected-(JP16-Pad2)") (class "Default")
      (node (ref "JP16") (pin "2") (pinfunction "2_2") (pintype "passive"))
    )
    (net (code "379") (name "unconnected-(JP16-Pad3)") (class "Default")
      (node (ref "JP16") (pin "3") (pinfunction "3_3") (pintype "passive"))
    )
    (net (code "380") (name "unconnected-(JP16-Pad4)") (class "Default")
      (node (ref "JP16") (pin "4") (pinfunction "4_4") (pintype "passive"))
    )
    (net (code "381") (name "unconnected-(JP16-Pad5)") (class "Default")
      (node (ref "JP16") (pin "5") (pinfunction "5_5") (pintype "passive"))
    )
    (net (code "382") (name "unconnected-(JP16-Pad6)") (class "Default")
      (node (ref "JP16") (pin "6") (pinfunction "6_6") (pintype "passive"))
    )
    (net (code "383") (name "unconnected-(JP16-Pad11)") (class "Default")
      (node (ref "JP16") (pin "11") (pinfunction "11_11") (pintype "passive"))
    )
    (net (code "384") (name "unconnected-(JP16-Pad14)") (class "Default")
      (node (ref "JP16") (pin "14") (pinfunction "14_14") (pintype "passive"))
    )
    (net (code "385") (name "unconnected-(JP16-Pad15)") (class "Default")
      (node (ref "JP16") (pin "15") (pinfunction "15_15") (pintype "passive"))
    )
    (net (code "386") (name "unconnected-(JP16-Pad16)") (class "Default")
      (node (ref "JP16") (pin "16") (pinfunction "16_16") (pintype "passive"))
    )
    (net (code "387") (name "unconnected-(JP16-Pad17)") (class "Default")
      (node (ref "JP16") (pin "17") (pinfunction "17_17") (pintype "passive"))
    )
    (net (code "388") (name "unconnected-(JP16-Pad18)") (class "Default")
      (node (ref "JP16") (pin "18") (pinfunction "18_18") (pintype "passive"))
    )
    (net (code "389") (name "unconnected-(JP16-Pad19)") (class "Default")
      (node (ref "JP16") (pin "19") (pinfunction "19_19") (pintype "passive"))
    )
    (net (code "390") (name "unconnected-(JP16-Pad20)") (class "Default")
      (node (ref "JP16") (pin "20") (pinfunction "20_20") (pintype "passive"))
    )
    (net (code "391") (name "unconnected-(M1-A-Pad1)") (class "Default")
      (node (ref "M1") (pin "1") (pinfunction "A_1") (pintype "bidirectional"))
    )
    (net (code "392") (name "unconnected-(M1-B-Pad2)") (class "Default")
      (node (ref "M1") (pin "2") (pinfunction "B_2") (pintype "bidirectional"))
    )
    (net (code "393") (name "unconnected-(M1-C-Pad3)") (class "Default")
      (node (ref "M1") (pin "3") (pinfunction "C_3") (pintype "bidirectional"))
    )
    (net (code "394") (name "unconnected-(M1-P$7-Pad7)") (class "Default")
      (node (ref "M1") (pin "7") (pinfunction "P$7_7") (pintype "bidirectional"))
    )
    (net (code "395") (name "unconnected-(MC-1-A-Pad1)") (class "Default")
      (node (ref "MC-1") (pin "1") (pinfunction "A_1") (pintype "bidirectional"))
    )
    (net (code "396") (name "unconnected-(MC-1-B-Pad2)") (class "Default")
      (node (ref "MC-1") (pin "2") (pinfunction "B_2") (pintype "bidirectional"))
    )
    (net (code "397") (name "unconnected-(MC-1-C-Pad3)") (class "Default")
      (node (ref "MC-1") (pin "3") (pinfunction "C_3") (pintype "bidirectional"))
    )
    (net (code "398") (name "unconnected-(MC-1-HV+-Pad4)") (class "Default")
      (node (ref "MC-1") (pin "4") (pinfunction "HV+_4") (pintype "bidirectional"))
    )
    (net (code "399") (name "unconnected-(MC-1-HV--Pad5)") (class "Default")
      (node (ref "MC-1") (pin "5") (pinfunction "HV-_5") (pintype "bidirectional"))
    )
    (net (code "400") (name "unconnected-(MCS-Pad12)") (class "Default")
      (node (ref "MCS") (pin "12") (pinfunction "12_12") (pintype "passive"))
    )
    (net (code "401") (name "unconnected-(MCSB-1-Pad13)") (class "Default")
      (node (ref "MCS") (pin "13") (pinfunction "1_13") (pintype "passive"))
    )
    (net (code "402") (name "unconnected-(MCSB-2-Pad14)") (class "Default")
      (node (ref "MCS") (pin "14") (pinfunction "2_14") (pintype "passive"))
    )
    (net (code "403") (name "unconnected-(MCSB-3-Pad15)") (class "Default")
      (node (ref "MCS") (pin "15") (pinfunction "3_15") (pintype "passive"))
    )
    (net (code "404") (name "unconnected-(MCSB-4-Pad16)") (class "Default")
      (node (ref "MCS") (pin "16") (pinfunction "4_16") (pintype "passive"))
    )
    (net (code "405") (name "unconnected-(MCSB-5-Pad17)") (class "Default")
      (node (ref "MCS") (pin "17") (pinfunction "5_17") (pintype "passive"))
    )
    (net (code "406") (name "unconnected-(MCSB-9-Pad21)") (class "Default")
      (node (ref "MCS") (pin "21") (pinfunction "9_21") (pintype "passive"))
    )
    (net (code "407") (name "unconnected-(MCSB-11-Pad23)") (class "Default")
      (node (ref "MCS") (pin "23") (pinfunction "11_23") (pintype "passive"))
    )
    (net (code "408") (name "unconnected-(MCSB-12-Pad24)") (class "Default")
      (node (ref "MCS") (pin "24") (pinfunction "12_24") (pintype "passive"))
    )
    (net (code "409") (name "unconnected-(MCSC-3-Pad27)") (class "Default")
      (node (ref "MCS") (pin "27") (pinfunction "3_27") (pintype "passive"))
    )
    (net (code "410") (name "unconnected-(MCSC-4-Pad28)") (class "Default")
      (node (ref "MCS") (pin "28") (pinfunction "4_28") (pintype "passive"))
    )
    (net (code "411") (name "unconnected-(MCSC-5-Pad29)") (class "Default")
      (node (ref "MCS") (pin "29") (pinfunction "5_29") (pintype "passive"))
    )
    (net (code "412") (name "unconnected-(MCSD-4-Pad40)") (class "Default")
      (node (ref "MCS") (pin "40") (pinfunction "4_40") (pintype "passive"))
    )
    (net (code "413") (name "unconnected-(MCSD-5-Pad41)") (class "Default")
      (node (ref "MCS") (pin "41") (pinfunction "5_41") (pintype "passive"))
    )
    (net (code "414") (name "unconnected-(MCSD-7-Pad43)") (class "Default")
      (node (ref "MCS") (pin "43") (pinfunction "7_43") (pintype "passive"))
    )
    (net (code "415") (name "unconnected-(MCSD-8-Pad44)") (class "Default")
      (node (ref "MCS") (pin "44") (pinfunction "8_44") (pintype "passive"))
    )
    (net (code "416") (name "unconnected-(MCSD-10-Pad46)") (class "Default")
      (node (ref "MCS") (pin "46") (pinfunction "10_46") (pintype "passive"))
    )
    (net (code "417") (name "unconnected-(S18-Pad6)") (class "Default")
      (node (ref "S18") (pin "6") (pinfunction "6_6") (pintype "bidirectional"))
    )
    (net (code "418") (name "unconnected-(SAS-Pad1)") (class "Default")
      (node (ref "SAS") (pin "1") (pinfunction "1_1") (pintype "passive"))
    )
    (net (code "419") (name "unconnected-(SAS-Pad2)") (class "Default")
      (node (ref "SAS") (pin "2") (pinfunction "2_2") (pintype "passive"))
    )
    (net (code "420") (name "unconnected-(SAS-Pad3)") (class "Default")
      (node (ref "SAS") (pin "3") (pinfunction "3_3") (pintype "passive"))
    )
    (net (code "421") (name "unconnected-(SAS-Pad4)") (class "Default")
      (node (ref "SAS") (pin "4") (pinfunction "4_4") (pintype "passive"))
    )
    (net (code "422") (name "unconnected-(SAS-Pad5)") (class "Default")
      (node (ref "SAS") (pin "5") (pinfunction "5_5") (pintype "passive"))
    )
    (net (code "423") (name "unconnected-(SAS-Pad6)") (class "Default")
      (node (ref "SAS") (pin "6") (pinfunction "6_6") (pintype "passive"))
    )
    (net (code "424") (name "unconnected-(SAS-Pad7)") (class "Default")
      (node (ref "SAS") (pin "7") (pinfunction "7_7") (pintype "passive"))
    )
    (net (code "425") (name "unconnected-(SAS-Pad8)") (class "Default")
      (node (ref "SAS") (pin "8") (pinfunction "8_8") (pintype "passive"))
    )
    (net (code "426") (name "unconnected-(SAS-Pad9)") (class "Default")
      (node (ref "SAS") (pin "9") (pinfunction "9_9") (pintype "passive"))
    )
    (net (code "427") (name "unconnected-(SAS-Pad10)") (class "Default")
      (node (ref "SAS") (pin "10") (pinfunction "10_10") (pintype "passive"))
    )
    (net (code "428") (name "unconnected-(SAS-Pad11)") (class "Default")
      (node (ref "SAS") (pin "11") (pinfunction "11_11") (pintype "passive"))
    )
    (net (code "429") (name "unconnected-(SAS-Pad12)") (class "Default")
      (node (ref "SAS") (pin "12") (pinfunction "12_12") (pintype "passive"))
    )
    (net (code "430") (name "unconnected-(SASB-1-Pad13)") (class "Default")
      (node (ref "SAS") (pin "13") (pinfunction "1_13") (pintype "passive"))
    )
    (net (code "431") (name "unconnected-(SASB-2-Pad14)") (class "Default")
      (node (ref "SAS") (pin "14") (pinfunction "2_14") (pintype "passive"))
    )
    (net (code "432") (name "unconnected-(SASB-3-Pad15)") (class "Default")
      (node (ref "SAS") (pin "15") (pinfunction "3_15") (pintype "passive"))
    )
    (net (code "433") (name "unconnected-(SASB-4-Pad16)") (class "Default")
      (node (ref "SAS") (pin "16") (pinfunction "4_16") (pintype "passive"))
    )
    (net (code "434") (name "unconnected-(SASC-5-Pad29)") (class "Default")
      (node (ref "SAS") (pin "29") (pinfunction "5_29") (pintype "passive"))
    )
    (net (code "435") (name "unconnected-(SASC-6-Pad30)") (class "Default")
      (node (ref "SAS") (pin "30") (pinfunction "6_30") (pintype "passive"))
    )
    (net (code "436") (name "unconnected-(SASC-7-Pad31)") (class "Default")
      (node (ref "SAS") (pin "31") (pinfunction "7_31") (pintype "passive"))
    )
    (net (code "437") (name "unconnected-(SASC-8-Pad32)") (class "Default")
      (node (ref "SAS") (pin "32") (pinfunction "8_32") (pintype "passive"))
    )
    (net (code "438") (name "unconnected-(SASC-9-Pad33)") (class "Default")
      (node (ref "SAS") (pin "33") (pinfunction "9_33") (pintype "passive"))
    )
    (net (code "439") (name "unconnected-(SASC-10-Pad34)") (class "Default")
      (node (ref "SAS") (pin "34") (pinfunction "10_34") (pintype "passive"))
    )
    (net (code "440") (name "unconnected-(SASC-11-Pad35)") (class "Default")
      (node (ref "SAS") (pin "35") (pinfunction "11_35") (pintype "passive"))
    )
    (net (code "441") (name "unconnected-(SASC-12-Pad36)") (class "Default")
      (node (ref "SAS") (pin "36") (pinfunction "12_36") (pintype "passive"))
    )
    (net (code "442") (name "unconnected-(SASD-6-Pad42)") (class "Default")
      (node (ref "SAS") (pin "42") (pinfunction "6_42") (pintype "passive"))
    )
    (net (code "443") (name "unconnected-(SASD-7-Pad43)") (class "Default")
      (node (ref "SAS") (pin "43") (pinfunction "7_43") (pintype "passive"))
    )
    (net (code "444") (name "unconnected-(SASD-8-Pad44)") (class "Default")
      (node (ref "SAS") (pin "44") (pinfunction "8_44") (pintype "passive"))
    )
    (net (code "445") (name "unconnected-(SASD-9-Pad45)") (class "Default")
      (node (ref "SAS") (pin "45") (pinfunction "9_45") (pintype "passive"))
    )
    (net (code "446") (name "unconnected-(SASD-10-Pad46)") (class "Default")
      (node (ref "SAS") (pin "46") (pinfunction "10_46") (pintype "passive"))
    )
    (net (code "447") (name "unconnected-(SASD-11-Pad47)") (class "Default")
      (node (ref "SAS") (pin "47") (pinfunction "11_47") (pintype "passive"))
    )
    (net (code "448") (name "unconnected-(SASD-12-Pad48)") (class "Default")
      (node (ref "SAS") (pin "48") (pinfunction "12_48") (pintype "passive"))
    )
    (net (code "449") (name "unconnected-(TSAL-C-PadK)") (class "Default")
      (node (ref "TSAL") (pin "K") (pinfunction "C_K") (pintype "passive"))
    )
    (net (code "450") (name "unconnected-(TSAL-PadA)") (class "Default")
      (node (ref "TSAL") (pin "A") (pinfunction "A_A") (pintype "passive"))
    )
    (net (code "451") (name "unconnected-(TSS-1-Pad1)") (class "Default")
      (node (ref "TSS-1") (pin "1") (pinfunction "1_1") (pintype "passive"))
    )
    (net (code "452") (name "unconnected-(TSS-1-Pad2)") (class "Default")
      (node (ref "TSS-1") (pin "2") (pinfunction "2_2") (pintype "passive"))
    )
    (net (code "453") (name "unconnected-(TSS-1-Pad3)") (class "Default")
      (node (ref "TSS-1") (pin "3") (pinfunction "3_3") (pintype "passive"))
    )
    (net (code "454") (name "unconnected-(TSS-1-Pad4)") (class "Default")
      (node (ref "TSS-1") (pin "4") (pinfunction "4_4") (pintype "passive"))
    )
    (net (code "455") (name "unconnected-(TSS-1-Pad5)") (class "Default")
      (node (ref "TSS-1") (pin "5") (pinfunction "5_5") (pintype "passive"))
    )
    (net (code "456") (name "unconnected-(TSS-1-Pad6)") (class "Default")
      (node (ref "TSS-1") (pin "6") (pinfunction "6_6") (pintype "passive"))
    )
    (net (code "457") (name "unconnected-(TSS-1-Pad7)") (class "Default")
      (node (ref "TSS-1") (pin "7") (pinfunction "7_7") (pintype "passive"))
    )
    (net (code "458") (name "unconnected-(TSS-1-Pad8)") (class "Default")
      (node (ref "TSS-1") (pin "8") (pinfunction "8_8") (pintype "passive"))
    )
    (net (code "459") (name "unconnected-(TSS-1-Pad9)") (class "Default")
      (node (ref "TSS-1") (pin "9") (pinfunction "9_9") (pintype "passive"))
    )
    (net (code "460") (name "unconnected-(TSS-1-Pad10)") (class "Default")
      (node (ref "TSS-1") (pin "10") (pinfunction "10_10") (pintype "passive"))
    )
    (net (code "461") (name "unconnected-(TSS-1-Pad11)") (class "Default")
      (node (ref "TSS-1") (pin "11") (pinfunction "11_11") (pintype "passive"))
    )
    (net (code "462") (name "unconnected-(TSS-1-Pad12)") (class "Default")
      (node (ref "TSS-1") (pin "12") (pinfunction "12_12") (pintype "passive"))
    )
    (net (code "463") (name "unconnected-(TSS-1B-1-Pad13)") (class "Default")
      (node (ref "TSS-1") (pin "13") (pinfunction "1_13") (pintype "passive"))
    )
    (net (code "464") (name "unconnected-(TSS-1B-2-Pad14)") (class "Default")
      (node (ref "TSS-1") (pin "14") (pinfunction "2_14") (pintype "passive"))
    )
    (net (code "465") (name "unconnected-(TSS-1B-3-Pad15)") (class "Default")
      (node (ref "TSS-1") (pin "15") (pinfunction "3_15") (pintype "passive"))
    )
    (net (code "466") (name "unconnected-(TSS-1B-4-Pad16)") (class "Default")
      (node (ref "TSS-1") (pin "16") (pinfunction "4_16") (pintype "passive"))
    )
    (net (code "467") (name "unconnected-(TSS-1B-5-Pad17)") (class "Default")
      (node (ref "TSS-1") (pin "17") (pinfunction "5_17") (pintype "passive"))
    )
    (net (code "468") (name "unconnected-(TSS-1B-6-Pad18)") (class "Default")
      (node (ref "TSS-1") (pin "18") (pinfunction "6_18") (pintype "passive"))
    )
    (net (code "469") (name "unconnected-(TSS-1B-7-Pad19)") (class "Default")
      (node (ref "TSS-1") (pin "19") (pinfunction "7_19") (pintype "passive"))
    )
    (net (code "470") (name "unconnected-(TSS-1B-8-Pad20)") (class "Default")
      (node (ref "TSS-1") (pin "20") (pinfunction "8_20") (pintype "passive"))
    )
    (net (code "471") (name "unconnected-(TSS-1B-9-Pad21)") (class "Default")
      (node (ref "TSS-1") (pin "21") (pinfunction "9_21") (pintype "passive"))
    )
    (net (code "472") (name "unconnected-(TSS-1B-10-Pad22)") (class "Default")
      (node (ref "TSS-1") (pin "22") (pinfunction "10_22") (pintype "passive"))
    )
    (net (code "473") (name "unconnected-(TSS-1B-11-Pad23)") (class "Default")
      (node (ref "TSS-1") (pin "23") (pinfunction "11_23") (pintype "passive"))
    )
    (net (code "474") (name "unconnected-(TSS-1B-12-Pad24)") (class "Default")
      (node (ref "TSS-1") (pin "24") (pinfunction "12_24") (pintype "passive"))
    )
    (net (code "475") (name "unconnected-(TSS-1C-1-Pad25)") (class "Default")
      (node (ref "TSS-1") (pin "25") (pinfunction "1_25") (pintype "passive"))
    )
    (net (code "476") (name "unconnected-(TSS-1C-2-Pad26)") (class "Default")
      (node (ref "TSS-1") (pin "26") (pinfunction "2_26") (pintype "passive"))
    )
    (net (code "477") (name "unconnected-(TSS-1C-3-Pad27)") (class "Default")
      (node (ref "TSS-1") (pin "27") (pinfunction "3_27") (pintype "passive"))
    )
    (net (code "478") (name "unconnected-(TSS-1C-4-Pad28)") (class "Default")
      (node (ref "TSS-1") (pin "28") (pinfunction "4_28") (pintype "passive"))
    )
    (net (code "479") (name "unconnected-(TSS-1C-5-Pad29)") (class "Default")
      (node (ref "TSS-1") (pin "29") (pinfunction "5_29") (pintype "passive"))
    )
    (net (code "480") (name "unconnected-(TSS-1C-6-Pad30)") (class "Default")
      (node (ref "TSS-1") (pin "30") (pinfunction "6_30") (pintype "passive"))
    )
    (net (code "481") (name "unconnected-(TSS-1C-7-Pad31)") (class "Default")
      (node (ref "TSS-1") (pin "31") (pinfunction "7_31") (pintype "passive"))
    )
    (net (code "482") (name "unconnected-(TSS-1C-8-Pad32)") (class "Default")
      (node (ref "TSS-1") (pin "32") (pinfunction "8_32") (pintype "passive"))
    )
    (net (code "483") (name "unconnected-(TSS-1C-9-Pad33)") (class "Default")
      (node (ref "TSS-1") (pin "33") (pinfunction "9_33") (pintype "passive"))
    )
    (net (code "484") (name "unconnected-(TSS-1C-10-Pad34)") (class "Default")
      (node (ref "TSS-1") (pin "34") (pinfunction "10_34") (pintype "passive"))
    )
    (net (code "485") (name "unconnected-(TSS-1C-11-Pad35)") (class "Default")
      (node (ref "TSS-1") (pin "35") (pinfunction "11_35") (pintype "passive"))
    )
    (net (code "486") (name "unconnected-(TSS-1C-12-Pad36)") (class "Default")
      (node (ref "TSS-1") (pin "36") (pinfunction "12_36") (pintype "passive"))
    )
    (net (code "487") (name "unconnected-(TSS-1D-1-Pad37)") (class "Default")
      (node (ref "TSS-1") (pin "37") (pinfunction "1_37") (pintype "passive"))
    )
    (net (code "488") (name "unconnected-(TSS-1D-2-Pad38)") (class "Default")
      (node (ref "TSS-1") (pin "38") (pinfunction "2_38") (pintype "passive"))
    )
    (net (code "489") (name "unconnected-(TSS-1D-3-Pad39)") (class "Default")
      (node (ref "TSS-1") (pin "39") (pinfunction "3_39") (pintype "passive"))
    )
    (net (code "490") (name "unconnected-(TSS-1D-4-Pad40)") (class "Default")
      (node (ref "TSS-1") (pin "40") (pinfunction "4_40") (pintype "passive"))
    )
    (net (code "491") (name "unconnected-(TSS-1D-9-Pad45)") (class "Default")
      (node (ref "TSS-1") (pin "45") (pinfunction "9_45") (pintype "passive"))
    )
    (net (code "492") (name "unconnected-(TSS-1D-10-Pad46)") (class "Default")
      (node (ref "TSS-1") (pin "46") (pinfunction "10_46") (pintype "passive"))
    )
    (net (code "493") (name "unconnected-(TSS-1D-11-Pad47)") (class "Default")
      (node (ref "TSS-1") (pin "47") (pinfunction "11_47") (pintype "passive"))
    )
    (net (code "494") (name "unconnected-(TSS-1D-12-Pad48)") (class "Default")
      (node (ref "TSS-1") (pin "48") (pinfunction "12_48") (pintype "passive"))
    )
    (net (code "495") (name "unconnected-(TSS-2-Pad1)") (class "Default")
      (node (ref "TSS-2") (pin "1") (pinfunction "1_1") (pintype "passive"))
    )
    (net (code "496") (name "unconnected-(TSS-2-Pad2)") (class "Default")
      (node (ref "TSS-2") (pin "2") (pinfunction "2_2") (pintype "passive"))
    )
    (net (code "497") (name "unconnected-(TSS-2-Pad3)") (class "Default")
      (node (ref "TSS-2") (pin "3") (pinfunction "3_3") (pintype "passive"))
    )
    (net (code "498") (name "unconnected-(TSS-2-Pad4)") (class "Default")
      (node (ref "TSS-2") (pin "4") (pinfunction "4_4") (pintype "passive"))
    )
    (net (code "499") (name "unconnected-(TSS-2-Pad5)") (class "Default")
      (node (ref "TSS-2") (pin "5") (pinfunction "5_5") (pintype "passive"))
    )
    (net (code "500") (name "unconnected-(TSS-2-Pad6)") (class "Default")
      (node (ref "TSS-2") (pin "6") (pinfunction "6_6") (pintype "passive"))
    )
    (net (code "501") (name "unconnected-(TSS-2-Pad7)") (class "Default")
      (node (ref "TSS-2") (pin "7") (pinfunction "7_7") (pintype "passive"))
    )
    (net (code "502") (name "unconnected-(TSS-2-Pad8)") (class "Default")
      (node (ref "TSS-2") (pin "8") (pinfunction "8_8") (pintype "passive"))
    )
    (net (code "503") (name "unconnected-(TSS-2-Pad9)") (class "Default")
      (node (ref "TSS-2") (pin "9") (pinfunction "9_9") (pintype "passive"))
    )
    (net (code "504") (name "unconnected-(TSS-2-Pad10)") (class "Default")
      (node (ref "TSS-2") (pin "10") (pinfunction "10_10") (pintype "passive"))
    )
    (net (code "505") (name "unconnected-(TSS-2-Pad11)") (class "Default")
      (node (ref "TSS-2") (pin "11") (pinfunction "11_11") (pintype "passive"))
    )
    (net (code "506") (name "unconnected-(TSS-2-Pad12)") (class "Default")
      (node (ref "TSS-2") (pin "12") (pinfunction "12_12") (pintype "passive"))
    )
    (net (code "507") (name "unconnected-(TSS-2B-1-Pad13)") (class "Default")
      (node (ref "TSS-2") (pin "13") (pinfunction "1_13") (pintype "passive"))
    )
    (net (code "508") (name "unconnected-(TSS-2B-2-Pad14)") (class "Default")
      (node (ref "TSS-2") (pin "14") (pinfunction "2_14") (pintype "passive"))
    )
    (net (code "509") (name "unconnected-(TSS-2B-3-Pad15)") (class "Default")
      (node (ref "TSS-2") (pin "15") (pinfunction "3_15") (pintype "passive"))
    )
    (net (code "510") (name "unconnected-(TSS-2B-4-Pad16)") (class "Default")
      (node (ref "TSS-2") (pin "16") (pinfunction "4_16") (pintype "passive"))
    )
    (net (code "511") (name "unconnected-(TSS-2B-5-Pad17)") (class "Default")
      (node (ref "TSS-2") (pin "17") (pinfunction "5_17") (pintype "passive"))
    )
    (net (code "512") (name "unconnected-(TSS-2B-6-Pad18)") (class "Default")
      (node (ref "TSS-2") (pin "18") (pinfunction "6_18") (pintype "passive"))
    )
    (net (code "513") (name "unconnected-(TSS-2B-7-Pad19)") (class "Default")
      (node (ref "TSS-2") (pin "19") (pinfunction "7_19") (pintype "passive"))
    )
    (net (code "514") (name "unconnected-(TSS-2B-8-Pad20)") (class "Default")
      (node (ref "TSS-2") (pin "20") (pinfunction "8_20") (pintype "passive"))
    )
    (net (code "515") (name "unconnected-(TSS-2B-9-Pad21)") (class "Default")
      (node (ref "TSS-2") (pin "21") (pinfunction "9_21") (pintype "passive"))
    )
    (net (code "516") (name "unconnected-(TSS-2B-10-Pad22)") (class "Default")
      (node (ref "TSS-2") (pin "22") (pinfunction "10_22") (pintype "passive"))
    )
    (net (code "517") (name "unconnected-(TSS-2B-11-Pad23)") (class "Default")
      (node (ref "TSS-2") (pin "23") (pinfunction "11_23") (pintype "passive"))
    )
    (net (code "518") (name "unconnected-(TSS-2B-12-Pad24)") (class "Default")
      (node (ref "TSS-2") (pin "24") (pinfunction "12_24") (pintype "passive"))
    )
    (net (code "519") (name "unconnected-(TSS-2C-1-Pad25)") (class "Default")
      (node (ref "TSS-2") (pin "25") (pinfunction "1_25") (pintype "passive"))
    )
    (net (code "520") (name "unconnected-(TSS-2C-2-Pad26)") (class "Default")
      (node (ref "TSS-2") (pin "26") (pinfunction "2_26") (pintype "passive"))
    )
    (net (code "521") (name "unconnected-(TSS-2C-3-Pad27)") (class "Default")
      (node (ref "TSS-2") (pin "27") (pinfunction "3_27") (pintype "passive"))
    )
    (net (code "522") (name "unconnected-(TSS-2C-4-Pad28)") (class "Default")
      (node (ref "TSS-2") (pin "28") (pinfunction "4_28") (pintype "passive"))
    )
    (net (code "523") (name "unconnected-(TSS-2C-5-Pad29)") (class "Default")
      (node (ref "TSS-2") (pin "29") (pinfunction "5_29") (pintype "passive"))
    )
    (net (code "524") (name "unconnected-(TSS-2C-6-Pad30)") (class "Default")
      (node (ref "TSS-2") (pin "30") (pinfunction "6_30") (pintype "passive"))
    )
    (net (code "525") (name "unconnected-(TSS-2C-7-Pad31)") (class "Default")
      (node (ref "TSS-2") (pin "31") (pinfunction "7_31") (pintype "passive"))
    )
    (net (code "526") (name "unconnected-(TSS-2C-8-Pad32)") (class "Default")
      (node (ref "TSS-2") (pin "32") (pinfunction "8_32") (pintype "passive"))
    )
    (net (code "527") (name "unconnected-(TSS-2C-9-Pad33)") (class "Default")
      (node (ref "TSS-2") (pin "33") (pinfunction "9_33") (pintype "passive"))
    )
    (net (code "528") (name "unconnected-(TSS-2C-10-Pad34)") (class "Default")
      (node (ref "TSS-2") (pin "34") (pinfunction "10_34") (pintype "passive"))
    )
    (net (code "529") (name "unconnected-(TSS-2C-11-Pad35)") (class "Default")
      (node (ref "TSS-2") (pin "35") (pinfunction "11_35") (pintype "passive"))
    )
    (net (code "530") (name "unconnected-(TSS-2C-12-Pad36)") (class "Default")
      (node (ref "TSS-2") (pin "36") (pinfunction "12_36") (pintype "passive"))
    )
    (net (code "531") (name "unconnected-(TSS-2D-1-Pad37)") (class "Default")
      (node (ref "TSS-2") (pin "37") (pinfunction "1_37") (pintype "passive"))
    )
    (net (code "532") (name "unconnected-(TSS-2D-2-Pad38)") (class "Default")
      (node (ref "TSS-2") (pin "38") (pinfunction "2_38") (pintype "passive"))
    )
    (net (code "533") (name "unconnected-(TSS-2D-3-Pad39)") (class "Default")
      (node (ref "TSS-2") (pin "39") (pinfunction "3_39") (pintype "passive"))
    )
    (net (code "534") (name "unconnected-(TSS-2D-4-Pad40)") (class "Default")
      (node (ref "TSS-2") (pin "40") (pinfunction "4_40") (pintype "passive"))
    )
    (net (code "535") (name "unconnected-(TSS-2D-9-Pad45)") (class "Default")
      (node (ref "TSS-2") (pin "45") (pinfunction "9_45") (pintype "passive"))
    )
    (net (code "536") (name "unconnected-(TSS-2D-10-Pad46)") (class "Default")
      (node (ref "TSS-2") (pin "46") (pinfunction "10_46") (pintype "passive"))
    )
    (net (code "537") (name "unconnected-(TSS-2D-11-Pad47)") (class "Default")
      (node (ref "TSS-2") (pin "47") (pinfunction "11_47") (pintype "passive"))
    )
    (net (code "538") (name "unconnected-(TSS-2D-12-Pad48)") (class "Default")
      (node (ref "TSS-2") (pin "48") (pinfunction "12_48") (pintype "passive"))
    )
    (net (code "539") (name "unconnected-(U$1-DATA-HIGH-PadP$5)") (class "Default")
      (node (ref "U$1") (pin "P$5") (pinfunction "DATA-HIGH_P$5") (pintype "bidirectional"))
    )
    (net (code "540") (name "unconnected-(U$1-DATA-LOW-PadP$6)") (class "Default")
      (node (ref "U$1") (pin "P$6") (pinfunction "DATA-LOW_P$6") (pintype "bidirectional"))
    )
  )
)
